# 10_FPGA_power.net
KiCad netlist of a schematic drawn in Altium Designer
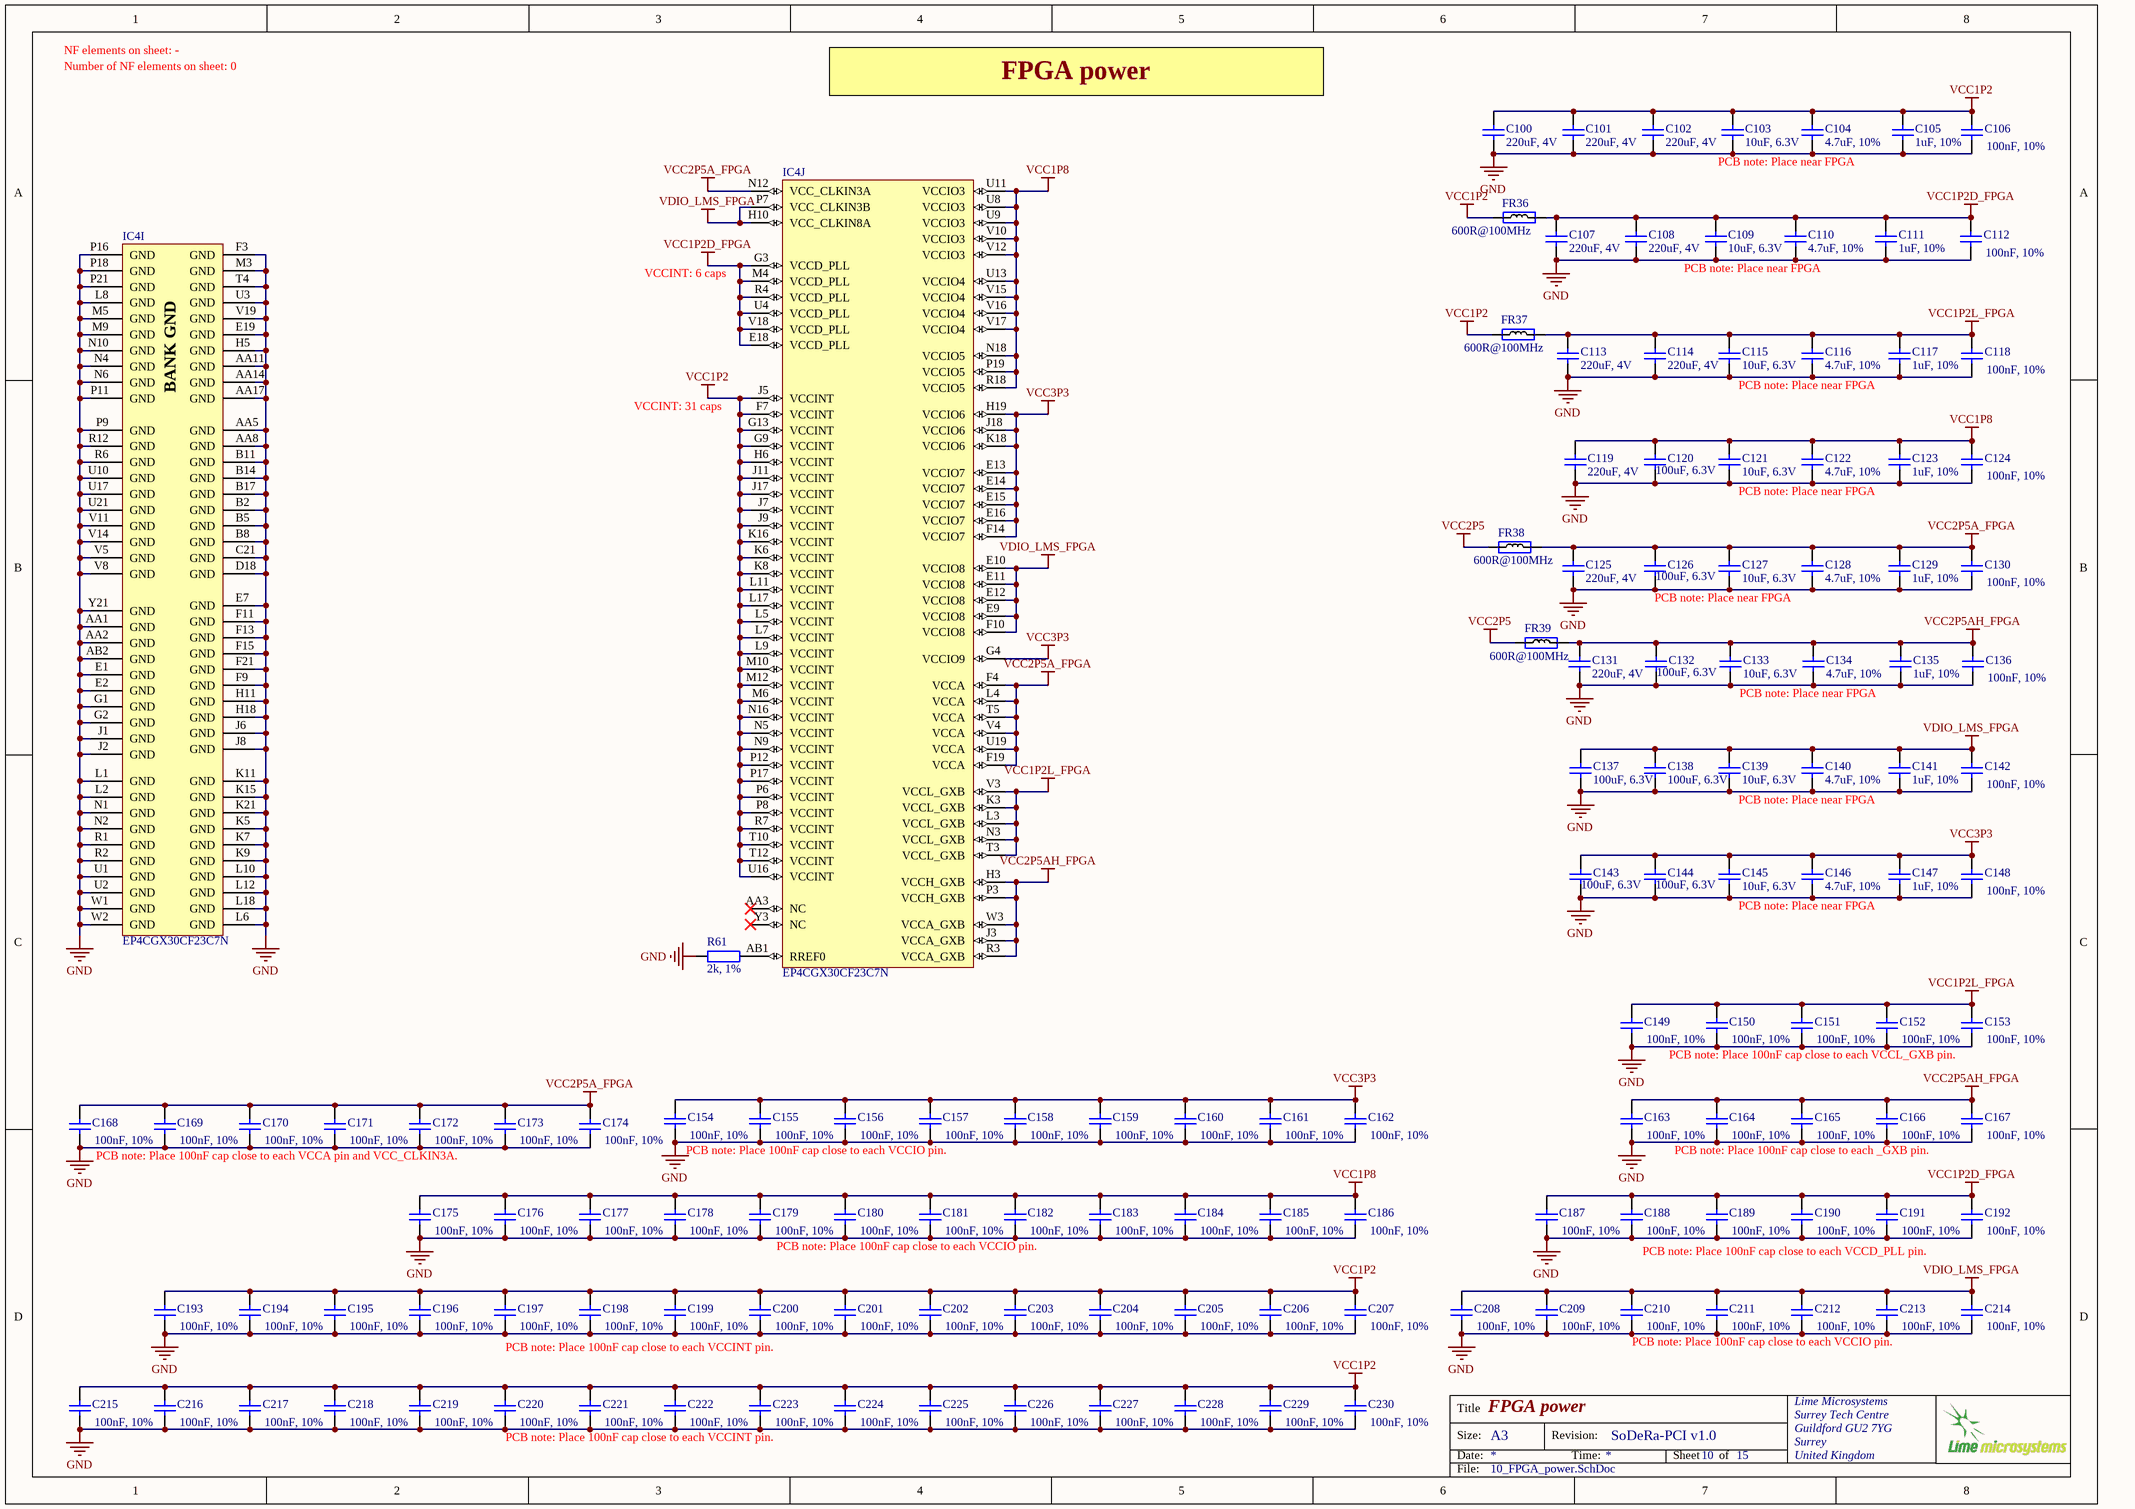
[diagram p0: 10_FPGA_power.SchDoc]

(export (version "E")
  (design (tool "Eeschema 10.0.6"))
  (components
    (comp (ref "C100")
      (value "220uF, 4V")
      (footprint "LimeMicroAltiumLib_pcbLib:CAP1206")
      (fields
        (field (name "MANUFACTURER PART NUMBER") "GRM31CR60G227ME11L")
        (field (name "MANUFACTURER") "Murata Electronics North America")
        (field (name "TOLERANCE") "±20%")
      )
      (libsource (lib "LimeFPGAboard_schLib") (part "Cap_1206"))
    )
    (comp (ref "C101")
      (value "220uF, 4V")
      (footprint "LimeMicroAltiumLib_pcbLib:CAP1206")
      (fields
        (field (name "MANUFACTURER PART NUMBER") "GRM31CR60G227ME11L")
        (field (name "MANUFACTURER") "Murata Electronics North America")
        (field (name "TOLERANCE") "±20%")
      )
      (libsource (lib "LimeFPGAboard_schLib") (part "Cap_1206"))
    )
    (comp (ref "C102")
      (value "220uF, 4V")
      (footprint "LimeMicroAltiumLib_pcbLib:CAP1206")
      (fields
        (field (name "MANUFACTURER PART NUMBER") "GRM31CR60G227ME11L")
        (field (name "MANUFACTURER") "Murata Electronics North America")
        (field (name "TOLERANCE") "±20%")
      )
      (libsource (lib "LimeFPGAboard_schLib") (part "Cap_1206"))
    )
    (comp (ref "C103")
      (value "10uF, 6.3V")
      (footprint "LimeMicroAltiumLib_pcbLib:CAP0603")
      (fields (field (name "TOLERANCE") "±20%"))
      (libsource (lib "LimeFPGAboard_schLib") (part "Cap_0603"))
    )
    (comp (ref "C104")
      (value "4.7uF, 10%")
      (footprint "LimeMicroAltiumLib_pcbLib:CAP0603")
      (fields (field (name "TOLERANCE") "10 %"))
      (libsource (lib "LimeFPGAboard_schLib") (part "Cap_0603"))
    )
    (comp (ref "C105")
      (value "1uF, 10%")
      (footprint "LimeMicroAltiumLib_pcbLib:CAP0402")
      (fields (field (name "MANUFACTURER") "TDK"))
      (libsource (lib "LimeMicroAltiumLib_schLib") (part "Cap_0402"))
    )
    (comp (ref "C106")
      (value "100nF, 10%")
      (footprint "LimeMicroAltiumLib_pcbLib:CAP0402")
      (fields
        (field (name "TOLERANCE") "10 %")
        (field (name "MANUFACTURER") "Murata")
        (field (name "MANUFACTURER PART NUMBER") "GRM155R71C104KA88D")
      )
      (libsource (lib "LimeFPGAboard_schLib") (part "Cap_0603"))
    )
    (comp (ref "C107")
      (value "220uF, 4V")
      (footprint "LimeMicroAltiumLib_pcbLib:CAP1206")
      (fields
        (field (name "MANUFACTURER PART NUMBER") "GRM31CR60G227ME11L")
        (field (name "MANUFACTURER") "Murata Electronics North America")
        (field (name "TOLERANCE") "±20%")
      )
      (libsource (lib "LimeFPGAboard_schLib") (part "Cap_1206"))
    )
    (comp (ref "C108")
      (value "220uF, 4V")
      (footprint "LimeMicroAltiumLib_pcbLib:CAP1206")
      (fields
        (field (name "MANUFACTURER PART NUMBER") "GRM31CR60G227ME11L")
        (field (name "MANUFACTURER") "Murata Electronics North America")
        (field (name "TOLERANCE") "±20%")
      )
      (libsource (lib "LimeFPGAboard_schLib") (part "Cap_1206"))
    )
    (comp (ref "C109")
      (value "10uF, 6.3V")
      (footprint "LimeMicroAltiumLib_pcbLib:CAP0603")
      (fields (field (name "TOLERANCE") "±20%"))
      (libsource (lib "LimeFPGAboard_schLib") (part "Cap_0603"))
    )
    (comp (ref "C110")
      (value "4.7uF, 10%")
      (footprint "LimeMicroAltiumLib_pcbLib:CAP0603")
      (fields (field (name "TOLERANCE") "10 %"))
      (libsource (lib "LimeFPGAboard_schLib") (part "Cap_0603"))
    )
    (comp (ref "C111")
      (value "1uF, 10%")
      (footprint "LimeMicroAltiumLib_pcbLib:CAP0402")
      (fields (field (name "MANUFACTURER") "TDK"))
      (libsource (lib "LimeMicroAltiumLib_schLib") (part "Cap_0402"))
    )
    (comp (ref "C112")
      (value "100nF, 10%")
      (footprint "LimeMicroAltiumLib_pcbLib:CAP0402")
      (fields
        (field (name "TOLERANCE") "10 %")
        (field (name "MANUFACTURER") "Murata")
        (field (name "MANUFACTURER PART NUMBER") "GRM155R71C104KA88D")
      )
      (libsource (lib "LimeFPGAboard_schLib") (part "Cap_0603"))
    )
    (comp (ref "C113")
      (value "220uF, 4V")
      (footprint "LimeMicroAltiumLib_pcbLib:CAP1206")
      (fields
        (field (name "MANUFACTURER PART NUMBER") "GRM31CR60G227ME11L")
        (field (name "MANUFACTURER") "Murata Electronics North America")
        (field (name "TOLERANCE") "±20%")
      )
      (libsource (lib "LimeFPGAboard_schLib") (part "Cap_1206"))
    )
    (comp (ref "C114")
      (value "220uF, 4V")
      (footprint "LimeMicroAltiumLib_pcbLib:CAP1206")
      (fields
        (field (name "MANUFACTURER PART NUMBER") "GRM31CR60G227ME11L")
        (field (name "MANUFACTURER") "Murata Electronics North America")
        (field (name "TOLERANCE") "±20%")
      )
      (libsource (lib "LimeFPGAboard_schLib") (part "Cap_1206"))
    )
    (comp (ref "C115")
      (value "10uF, 6.3V")
      (footprint "LimeMicroAltiumLib_pcbLib:CAP0603")
      (fields (field (name "TOLERANCE") "±20%"))
      (libsource (lib "LimeFPGAboard_schLib") (part "Cap_0603"))
    )
    (comp (ref "C116")
      (value "4.7uF, 10%")
      (footprint "LimeMicroAltiumLib_pcbLib:CAP0603")
      (fields (field (name "TOLERANCE") "10 %"))
      (libsource (lib "LimeFPGAboard_schLib") (part "Cap_0603"))
    )
    (comp (ref "C117")
      (value "1uF, 10%")
      (footprint "LimeMicroAltiumLib_pcbLib:CAP0402")
      (fields (field (name "MANUFACTURER") "TDK"))
      (libsource (lib "LimeMicroAltiumLib_schLib") (part "Cap_0402"))
    )
    (comp (ref "C118")
      (value "100nF, 10%")
      (footprint "LimeMicroAltiumLib_pcbLib:CAP0402")
      (fields
        (field (name "TOLERANCE") "10 %")
        (field (name "MANUFACTURER") "Murata")
        (field (name "MANUFACTURER PART NUMBER") "GRM155R71C104KA88D")
      )
      (libsource (lib "LimeFPGAboard_schLib") (part "Cap_0603"))
    )
    (comp (ref "C119")
      (value "220uF, 4V")
      (footprint "LimeMicroAltiumLib_pcbLib:CAP1206")
      (fields
        (field (name "MANUFACTURER PART NUMBER") "GRM31CR60G227ME11L")
        (field (name "MANUFACTURER") "Murata Electronics North America")
        (field (name "TOLERANCE") "±20%")
      )
      (libsource (lib "LimeFPGAboard_schLib") (part "Cap_1206"))
    )
    (comp (ref "C120")
      (value "100uF, 6.3V")
      (footprint "LimeMicroAltiumLib_pcbLib:CAP1206")
      (fields (field (name "MANUFACTURER") "MURATA"))
      (libsource (lib "LimeFPGAboard_schLib") (part "Cap_1206"))
    )
    (comp (ref "C121")
      (value "10uF, 6.3V")
      (footprint "LimeMicroAltiumLib_pcbLib:CAP0603")
      (fields (field (name "TOLERANCE") "±20%"))
      (libsource (lib "LimeFPGAboard_schLib") (part "Cap_0603"))
    )
    (comp (ref "C122")
      (value "4.7uF, 10%")
      (footprint "LimeMicroAltiumLib_pcbLib:CAP0603")
      (fields (field (name "TOLERANCE") "10 %"))
      (libsource (lib "LimeFPGAboard_schLib") (part "Cap_0603"))
    )
    (comp (ref "C123")
      (value "1uF, 10%")
      (footprint "LimeMicroAltiumLib_pcbLib:CAP0402")
      (fields (field (name "MANUFACTURER") "TDK"))
      (libsource (lib "LimeMicroAltiumLib_schLib") (part "Cap_0402"))
    )
    (comp (ref "C124")
      (value "100nF, 10%")
      (footprint "LimeMicroAltiumLib_pcbLib:CAP0402")
      (fields
        (field (name "TOLERANCE") "10 %")
        (field (name "MANUFACTURER") "Murata")
        (field (name "MANUFACTURER PART NUMBER") "GRM155R71C104KA88D")
      )
      (libsource (lib "LimeFPGAboard_schLib") (part "Cap_0603"))
    )
    (comp (ref "C125")
      (value "220uF, 4V")
      (footprint "LimeMicroAltiumLib_pcbLib:CAP1206")
      (fields
        (field (name "MANUFACTURER PART NUMBER") "GRM31CR60G227ME11L")
        (field (name "MANUFACTURER") "Murata Electronics North America")
        (field (name "TOLERANCE") "±20%")
      )
      (libsource (lib "LimeFPGAboard_schLib") (part "Cap_1206"))
    )
    (comp (ref "C126")
      (value "100uF, 6.3V")
      (footprint "LimeMicroAltiumLib_pcbLib:CAP1206")
      (fields (field (name "MANUFACTURER") "MURATA"))
      (libsource (lib "LimeFPGAboard_schLib") (part "Cap_1206"))
    )
    (comp (ref "C127")
      (value "10uF, 6.3V")
      (footprint "LimeMicroAltiumLib_pcbLib:CAP0603")
      (fields (field (name "TOLERANCE") "±20%"))
      (libsource (lib "LimeFPGAboard_schLib") (part "Cap_0603"))
    )
    (comp (ref "C128")
      (value "4.7uF, 10%")
      (footprint "LimeMicroAltiumLib_pcbLib:CAP0603")
      (fields (field (name "TOLERANCE") "10 %"))
      (libsource (lib "LimeFPGAboard_schLib") (part "Cap_0603"))
    )
    (comp (ref "C129")
      (value "1uF, 10%")
      (footprint "LimeMicroAltiumLib_pcbLib:CAP0402")
      (fields (field (name "MANUFACTURER") "TDK"))
      (libsource (lib "LimeMicroAltiumLib_schLib") (part "Cap_0402"))
    )
    (comp (ref "C130")
      (value "100nF, 10%")
      (footprint "LimeMicroAltiumLib_pcbLib:CAP0402")
      (fields
        (field (name "TOLERANCE") "10 %")
        (field (name "MANUFACTURER") "Murata")
        (field (name "MANUFACTURER PART NUMBER") "GRM155R71C104KA88D")
      )
      (libsource (lib "LimeFPGAboard_schLib") (part "Cap_0603"))
    )
    (comp (ref "C131")
      (value "220uF, 4V")
      (footprint "LimeMicroAltiumLib_pcbLib:CAP1206")
      (fields
        (field (name "MANUFACTURER PART NUMBER") "GRM31CR60G227ME11L")
        (field (name "MANUFACTURER") "Murata Electronics North America")
        (field (name "TOLERANCE") "±20%")
      )
      (libsource (lib "LimeFPGAboard_schLib") (part "Cap_1206"))
    )
    (comp (ref "C132")
      (value "100uF, 6.3V")
      (footprint "LimeMicroAltiumLib_pcbLib:CAP1206")
      (fields (field (name "MANUFACTURER") "MURATA"))
      (libsource (lib "LimeFPGAboard_schLib") (part "Cap_1206"))
    )
    (comp (ref "C133")
      (value "10uF, 6.3V")
      (footprint "LimeMicroAltiumLib_pcbLib:CAP0603")
      (fields (field (name "TOLERANCE") "±20%"))
      (libsource (lib "LimeFPGAboard_schLib") (part "Cap_0603"))
    )
    (comp (ref "C134")
      (value "4.7uF, 10%")
      (footprint "LimeMicroAltiumLib_pcbLib:CAP0603")
      (fields (field (name "TOLERANCE") "10 %"))
      (libsource (lib "LimeFPGAboard_schLib") (part "Cap_0603"))
    )
    (comp (ref "C135")
      (value "1uF, 10%")
      (footprint "LimeMicroAltiumLib_pcbLib:CAP0402")
      (fields (field (name "MANUFACTURER") "TDK"))
      (libsource (lib "LimeMicroAltiumLib_schLib") (part "Cap_0402"))
    )
    (comp (ref "C136")
      (value "100nF, 10%")
      (footprint "LimeMicroAltiumLib_pcbLib:CAP0402")
      (fields
        (field (name "TOLERANCE") "10 %")
        (field (name "MANUFACTURER") "Murata")
        (field (name "MANUFACTURER PART NUMBER") "GRM155R71C104KA88D")
      )
      (libsource (lib "LimeFPGAboard_schLib") (part "Cap_0603"))
    )
    (comp (ref "C137")
      (value "100uF, 6.3V")
      (footprint "LimeMicroAltiumLib_pcbLib:CAP1206")
      (fields (field (name "MANUFACTURER") "MURATA"))
      (libsource (lib "LimeFPGAboard_schLib") (part "Cap_1206"))
    )
    (comp (ref "C138")
      (value "100uF, 6.3V")
      (footprint "LimeMicroAltiumLib_pcbLib:CAP1206")
      (fields (field (name "MANUFACTURER") "MURATA"))
      (libsource (lib "LimeFPGAboard_schLib") (part "Cap_1206"))
    )
    (comp (ref "C139")
      (value "10uF, 6.3V")
      (footprint "LimeMicroAltiumLib_pcbLib:CAP0603")
      (fields (field (name "TOLERANCE") "±20%"))
      (libsource (lib "LimeFPGAboard_schLib") (part "Cap_0603"))
    )
    (comp (ref "C140")
      (value "4.7uF, 10%")
      (footprint "LimeMicroAltiumLib_pcbLib:CAP0603")
      (fields (field (name "TOLERANCE") "10 %"))
      (libsource (lib "LimeFPGAboard_schLib") (part "Cap_0603"))
    )
    (comp (ref "C141")
      (value "1uF, 10%")
      (footprint "LimeMicroAltiumLib_pcbLib:CAP0402")
      (fields (field (name "MANUFACTURER") "TDK"))
      (libsource (lib "LimeMicroAltiumLib_schLib") (part "Cap_0402"))
    )
    (comp (ref "C142")
      (value "100nF, 10%")
      (footprint "LimeMicroAltiumLib_pcbLib:CAP0402")
      (fields
        (field (name "TOLERANCE") "10 %")
        (field (name "MANUFACTURER") "Murata")
        (field (name "MANUFACTURER PART NUMBER") "GRM155R71C104KA88D")
      )
      (libsource (lib "LimeFPGAboard_schLib") (part "Cap_0603"))
    )
    (comp (ref "C143")
      (value "100uF, 6.3V")
      (footprint "LimeMicroAltiumLib_pcbLib:CAP1206")
      (fields (field (name "MANUFACTURER") "MURATA"))
      (libsource (lib "LimeFPGAboard_schLib") (part "Cap_1206"))
    )
    (comp (ref "C144")
      (value "100uF, 6.3V")
      (footprint "LimeMicroAltiumLib_pcbLib:CAP1206")
      (fields (field (name "MANUFACTURER") "MURATA"))
      (libsource (lib "LimeFPGAboard_schLib") (part "Cap_1206"))
    )
    (comp (ref "C145")
      (value "10uF, 6.3V")
      (footprint "LimeMicroAltiumLib_pcbLib:CAP0603")
      (fields (field (name "TOLERANCE") "±20%"))
      (libsource (lib "LimeFPGAboard_schLib") (part "Cap_0603"))
    )
    (comp (ref "C146")
      (value "4.7uF, 10%")
      (footprint "LimeMicroAltiumLib_pcbLib:CAP0603")
      (fields (field (name "TOLERANCE") "10 %"))
      (libsource (lib "LimeFPGAboard_schLib") (part "Cap_0603"))
    )
    (comp (ref "C147")
      (value "1uF, 10%")
      (footprint "LimeMicroAltiumLib_pcbLib:CAP0402")
      (fields (field (name "MANUFACTURER") "TDK"))
      (libsource (lib "LimeMicroAltiumLib_schLib") (part "Cap_0402"))
    )
    (comp (ref "C148")
      (value "100nF, 10%")
      (footprint "LimeMicroAltiumLib_pcbLib:CAP0402")
      (fields
        (field (name "TOLERANCE") "10 %")
        (field (name "MANUFACTURER") "Murata")
        (field (name "MANUFACTURER PART NUMBER") "GRM155R71C104KA88D")
      )
      (libsource (lib "LimeFPGAboard_schLib") (part "Cap_0603"))
    )
    (comp (ref "C149")
      (value "100nF, 10%")
      (footprint "LimeMicroAltiumLib_pcbLib:CAP0402")
      (fields
        (field (name "TOLERANCE") "10 %")
        (field (name "MANUFACTURER") "Murata")
        (field (name "MANUFACTURER PART NUMBER") "GRM155R71C104KA88D")
      )
      (libsource (lib "LimeFPGAboard_schLib") (part "Cap_0603"))
    )
    (comp (ref "C150")
      (value "100nF, 10%")
      (footprint "LimeMicroAltiumLib_pcbLib:CAP0402")
      (fields
        (field (name "TOLERANCE") "10 %")
        (field (name "MANUFACTURER") "Murata")
        (field (name "MANUFACTURER PART NUMBER") "GRM155R71C104KA88D")
      )
      (libsource (lib "LimeFPGAboard_schLib") (part "Cap_0603"))
    )
    (comp (ref "C151")
      (value "100nF, 10%")
      (footprint "LimeMicroAltiumLib_pcbLib:CAP0402")
      (fields
        (field (name "TOLERANCE") "10 %")
        (field (name "MANUFACTURER") "Murata")
        (field (name "MANUFACTURER PART NUMBER") "GRM155R71C104KA88D")
      )
      (libsource (lib "LimeFPGAboard_schLib") (part "Cap_0603"))
    )
    (comp (ref "C152")
      (value "100nF, 10%")
      (footprint "LimeMicroAltiumLib_pcbLib:CAP0402")
      (fields
        (field (name "TOLERANCE") "10 %")
        (field (name "MANUFACTURER") "Murata")
        (field (name "MANUFACTURER PART NUMBER") "GRM155R71C104KA88D")
      )
      (libsource (lib "LimeFPGAboard_schLib") (part "Cap_0603"))
    )
    (comp (ref "C153")
      (value "100nF, 10%")
      (footprint "LimeMicroAltiumLib_pcbLib:CAP0402")
      (fields
        (field (name "TOLERANCE") "10 %")
        (field (name "MANUFACTURER") "Murata")
        (field (name "MANUFACTURER PART NUMBER") "GRM155R71C104KA88D")
      )
      (libsource (lib "LimeFPGAboard_schLib") (part "Cap_0603"))
    )
    (comp (ref "C154")
      (value "100nF, 10%")
      (footprint "LimeMicroAltiumLib_pcbLib:CAP0402")
      (fields
        (field (name "TOLERANCE") "10 %")
        (field (name "MANUFACTURER") "Murata")
        (field (name "MANUFACTURER PART NUMBER") "GRM155R71C104KA88D")
      )
      (libsource (lib "LimeFPGAboard_schLib") (part "Cap_0603"))
    )
    (comp (ref "C155")
      (value "100nF, 10%")
      (footprint "LimeMicroAltiumLib_pcbLib:CAP0402")
      (fields
        (field (name "TOLERANCE") "10 %")
        (field (name "MANUFACTURER") "Murata")
        (field (name "MANUFACTURER PART NUMBER") "GRM155R71C104KA88D")
      )
      (libsource (lib "LimeFPGAboard_schLib") (part "Cap_0603"))
    )
    (comp (ref "C156")
      (value "100nF, 10%")
      (footprint "LimeMicroAltiumLib_pcbLib:CAP0402")
      (fields
        (field (name "TOLERANCE") "10 %")
        (field (name "MANUFACTURER") "Murata")
        (field (name "MANUFACTURER PART NUMBER") "GRM155R71C104KA88D")
      )
      (libsource (lib "LimeFPGAboard_schLib") (part "Cap_0603"))
    )
    (comp (ref "C157")
      (value "100nF, 10%")
      (footprint "LimeMicroAltiumLib_pcbLib:CAP0402")
      (fields
        (field (name "TOLERANCE") "10 %")
        (field (name "MANUFACTURER") "Murata")
        (field (name "MANUFACTURER PART NUMBER") "GRM155R71C104KA88D")
      )
      (libsource (lib "LimeFPGAboard_schLib") (part "Cap_0603"))
    )
    (comp (ref "C158")
      (value "100nF, 10%")
      (footprint "LimeMicroAltiumLib_pcbLib:CAP0402")
      (fields
        (field (name "TOLERANCE") "10 %")
        (field (name "MANUFACTURER") "Murata")
        (field (name "MANUFACTURER PART NUMBER") "GRM155R71C104KA88D")
      )
      (libsource (lib "LimeFPGAboard_schLib") (part "Cap_0603"))
    )
    (comp (ref "C159")
      (value "100nF, 10%")
      (footprint "LimeMicroAltiumLib_pcbLib:CAP0402")
      (fields
        (field (name "TOLERANCE") "10 %")
        (field (name "MANUFACTURER") "Murata")
        (field (name "MANUFACTURER PART NUMBER") "GRM155R71C104KA88D")
      )
      (libsource (lib "LimeFPGAboard_schLib") (part "Cap_0603"))
    )
    (comp (ref "C160")
      (value "100nF, 10%")
      (footprint "LimeMicroAltiumLib_pcbLib:CAP0402")
      (fields
        (field (name "TOLERANCE") "10 %")
        (field (name "MANUFACTURER") "Murata")
        (field (name "MANUFACTURER PART NUMBER") "GRM155R71C104KA88D")
      )
      (libsource (lib "LimeFPGAboard_schLib") (part "Cap_0603"))
    )
    (comp (ref "C161")
      (value "100nF, 10%")
      (footprint "LimeMicroAltiumLib_pcbLib:CAP0402")
      (fields
        (field (name "TOLERANCE") "10 %")
        (field (name "MANUFACTURER") "Murata")
        (field (name "MANUFACTURER PART NUMBER") "GRM155R71C104KA88D")
      )
      (libsource (lib "LimeFPGAboard_schLib") (part "Cap_0603"))
    )
    (comp (ref "C162")
      (value "100nF, 10%")
      (footprint "LimeMicroAltiumLib_pcbLib:CAP0402")
      (fields
        (field (name "TOLERANCE") "10 %")
        (field (name "MANUFACTURER") "Murata")
        (field (name "MANUFACTURER PART NUMBER") "GRM155R71C104KA88D")
      )
      (libsource (lib "LimeFPGAboard_schLib") (part "Cap_0603"))
    )
    (comp (ref "C163")
      (value "100nF, 10%")
      (footprint "LimeMicroAltiumLib_pcbLib:CAP0402")
      (fields
        (field (name "TOLERANCE") "10 %")
        (field (name "MANUFACTURER") "Murata")
        (field (name "MANUFACTURER PART NUMBER") "GRM155R71C104KA88D")
      )
      (libsource (lib "LimeFPGAboard_schLib") (part "Cap_0603"))
    )
    (comp (ref "C164")
      (value "100nF, 10%")
      (footprint "LimeMicroAltiumLib_pcbLib:CAP0402")
      (fields
        (field (name "TOLERANCE") "10 %")
        (field (name "MANUFACTURER") "Murata")
        (field (name "MANUFACTURER PART NUMBER") "GRM155R71C104KA88D")
      )
      (libsource (lib "LimeFPGAboard_schLib") (part "Cap_0603"))
    )
    (comp (ref "C165")
      (value "100nF, 10%")
      (footprint "LimeMicroAltiumLib_pcbLib:CAP0402")
      (fields
        (field (name "TOLERANCE") "10 %")
        (field (name "MANUFACTURER") "Murata")
        (field (name "MANUFACTURER PART NUMBER") "GRM155R71C104KA88D")
      )
      (libsource (lib "LimeFPGAboard_schLib") (part "Cap_0603"))
    )
    (comp (ref "C166")
      (value "100nF, 10%")
      (footprint "LimeMicroAltiumLib_pcbLib:CAP0402")
      (fields
        (field (name "TOLERANCE") "10 %")
        (field (name "MANUFACTURER") "Murata")
        (field (name "MANUFACTURER PART NUMBER") "GRM155R71C104KA88D")
      )
      (libsource (lib "LimeFPGAboard_schLib") (part "Cap_0603"))
    )
    (comp (ref "C167")
      (value "100nF, 10%")
      (footprint "LimeMicroAltiumLib_pcbLib:CAP0402")
      (fields
        (field (name "TOLERANCE") "10 %")
        (field (name "MANUFACTURER") "Murata")
        (field (name "MANUFACTURER PART NUMBER") "GRM155R71C104KA88D")
      )
      (libsource (lib "LimeFPGAboard_schLib") (part "Cap_0603"))
    )
    (comp (ref "C168")
      (value "100nF, 10%")
      (footprint "LimeMicroAltiumLib_pcbLib:CAP0402")
      (fields
        (field (name "TOLERANCE") "10 %")
        (field (name "MANUFACTURER") "Murata")
        (field (name "MANUFACTURER PART NUMBER") "GRM155R71C104KA88D")
      )
      (libsource (lib "LimeFPGAboard_schLib") (part "Cap_0603"))
    )
    (comp (ref "C169")
      (value "100nF, 10%")
      (footprint "LimeMicroAltiumLib_pcbLib:CAP0402")
      (fields
        (field (name "TOLERANCE") "10 %")
        (field (name "MANUFACTURER") "Murata")
        (field (name "MANUFACTURER PART NUMBER") "GRM155R71C104KA88D")
      )
      (libsource (lib "LimeFPGAboard_schLib") (part "Cap_0603"))
    )
    (comp (ref "C170")
      (value "100nF, 10%")
      (footprint "LimeMicroAltiumLib_pcbLib:CAP0402")
      (fields
        (field (name "TOLERANCE") "10 %")
        (field (name "MANUFACTURER") "Murata")
        (field (name "MANUFACTURER PART NUMBER") "GRM155R71C104KA88D")
      )
      (libsource (lib "LimeFPGAboard_schLib") (part "Cap_0603"))
    )
    (comp (ref "C171")
      (value "100nF, 10%")
      (footprint "LimeMicroAltiumLib_pcbLib:CAP0402")
      (fields
        (field (name "TOLERANCE") "10 %")
        (field (name "MANUFACTURER") "Murata")
        (field (name "MANUFACTURER PART NUMBER") "GRM155R71C104KA88D")
      )
      (libsource (lib "LimeFPGAboard_schLib") (part "Cap_0603"))
    )
    (comp (ref "C172")
      (value "100nF, 10%")
      (footprint "LimeMicroAltiumLib_pcbLib:CAP0402")
      (fields
        (field (name "TOLERANCE") "10 %")
        (field (name "MANUFACTURER") "Murata")
        (field (name "MANUFACTURER PART NUMBER") "GRM155R71C104KA88D")
      )
      (libsource (lib "LimeFPGAboard_schLib") (part "Cap_0603"))
    )
    (comp (ref "C173")
      (value "100nF, 10%")
      (footprint "LimeMicroAltiumLib_pcbLib:CAP0402")
      (fields
        (field (name "TOLERANCE") "10 %")
        (field (name "MANUFACTURER") "Murata")
        (field (name "MANUFACTURER PART NUMBER") "GRM155R71C104KA88D")
      )
      (libsource (lib "LimeFPGAboard_schLib") (part "Cap_0603"))
    )
    (comp (ref "C174")
      (value "100nF, 10%")
      (footprint "LimeMicroAltiumLib_pcbLib:CAP0402")
      (fields
        (field (name "TOLERANCE") "10 %")
        (field (name "MANUFACTURER") "Murata")
        (field (name "MANUFACTURER PART NUMBER") "GRM155R71C104KA88D")
      )
      (libsource (lib "LimeFPGAboard_schLib") (part "Cap_0603"))
    )
    (comp (ref "C175")
      (value "100nF, 10%")
      (footprint "LimeMicroAltiumLib_pcbLib:CAP0402")
      (fields
        (field (name "TOLERANCE") "10 %")
        (field (name "MANUFACTURER") "Murata")
        (field (name "MANUFACTURER PART NUMBER") "GRM155R71C104KA88D")
      )
      (libsource (lib "LimeFPGAboard_schLib") (part "Cap_0603"))
    )
    (comp (ref "C176")
      (value "100nF, 10%")
      (footprint "LimeMicroAltiumLib_pcbLib:CAP0402")
      (fields
        (field (name "TOLERANCE") "10 %")
        (field (name "MANUFACTURER") "Murata")
        (field (name "MANUFACTURER PART NUMBER") "GRM155R71C104KA88D")
      )
      (libsource (lib "LimeFPGAboard_schLib") (part "Cap_0603"))
    )
    (comp (ref "C177")
      (value "100nF, 10%")
      (footprint "LimeMicroAltiumLib_pcbLib:CAP0402")
      (fields
        (field (name "TOLERANCE") "10 %")
        (field (name "MANUFACTURER") "Murata")
        (field (name "MANUFACTURER PART NUMBER") "GRM155R71C104KA88D")
      )
      (libsource (lib "LimeFPGAboard_schLib") (part "Cap_0603"))
    )
    (comp (ref "C178")
      (value "100nF, 10%")
      (footprint "LimeMicroAltiumLib_pcbLib:CAP0402")
      (fields
        (field (name "TOLERANCE") "10 %")
        (field (name "MANUFACTURER") "Murata")
        (field (name "MANUFACTURER PART NUMBER") "GRM155R71C104KA88D")
      )
      (libsource (lib "LimeFPGAboard_schLib") (part "Cap_0603"))
    )
    (comp (ref "C179")
      (value "100nF, 10%")
      (footprint "LimeMicroAltiumLib_pcbLib:CAP0402")
      (fields
        (field (name "TOLERANCE") "10 %")
        (field (name "MANUFACTURER") "Murata")
        (field (name "MANUFACTURER PART NUMBER") "GRM155R71C104KA88D")
      )
      (libsource (lib "LimeFPGAboard_schLib") (part "Cap_0603"))
    )
    (comp (ref "C180")
      (value "100nF, 10%")
      (footprint "LimeMicroAltiumLib_pcbLib:CAP0402")
      (fields
        (field (name "TOLERANCE") "10 %")
        (field (name "MANUFACTURER") "Murata")
        (field (name "MANUFACTURER PART NUMBER") "GRM155R71C104KA88D")
      )
      (libsource (lib "LimeFPGAboard_schLib") (part "Cap_0603"))
    )
    (comp (ref "C181")
      (value "100nF, 10%")
      (footprint "LimeMicroAltiumLib_pcbLib:CAP0402")
      (fields
        (field (name "TOLERANCE") "10 %")
        (field (name "MANUFACTURER") "Murata")
        (field (name "MANUFACTURER PART NUMBER") "GRM155R71C104KA88D")
      )
      (libsource (lib "LimeFPGAboard_schLib") (part "Cap_0603"))
    )
    (comp (ref "C182")
      (value "100nF, 10%")
      (footprint "LimeMicroAltiumLib_pcbLib:CAP0402")
      (fields
        (field (name "TOLERANCE") "10 %")
        (field (name "MANUFACTURER") "Murata")
        (field (name "MANUFACTURER PART NUMBER") "GRM155R71C104KA88D")
      )
      (libsource (lib "LimeFPGAboard_schLib") (part "Cap_0603"))
    )
    (comp (ref "C183")
      (value "100nF, 10%")
      (footprint "LimeMicroAltiumLib_pcbLib:CAP0402")
      (fields
        (field (name "TOLERANCE") "10 %")
        (field (name "MANUFACTURER") "Murata")
        (field (name "MANUFACTURER PART NUMBER") "GRM155R71C104KA88D")
      )
      (libsource (lib "LimeFPGAboard_schLib") (part "Cap_0603"))
    )
    (comp (ref "C184")
      (value "100nF, 10%")
      (footprint "LimeMicroAltiumLib_pcbLib:CAP0402")
      (fields
        (field (name "TOLERANCE") "10 %")
        (field (name "MANUFACTURER") "Murata")
        (field (name "MANUFACTURER PART NUMBER") "GRM155R71C104KA88D")
      )
      (libsource (lib "LimeFPGAboard_schLib") (part "Cap_0603"))
    )
    (comp (ref "C185")
      (value "100nF, 10%")
      (footprint "LimeMicroAltiumLib_pcbLib:CAP0402")
      (fields
        (field (name "TOLERANCE") "10 %")
        (field (name "MANUFACTURER") "Murata")
        (field (name "MANUFACTURER PART NUMBER") "GRM155R71C104KA88D")
      )
      (libsource (lib "LimeFPGAboard_schLib") (part "Cap_0603"))
    )
    (comp (ref "C186")
      (value "100nF, 10%")
      (footprint "LimeMicroAltiumLib_pcbLib:CAP0402")
      (fields
        (field (name "TOLERANCE") "10 %")
        (field (name "MANUFACTURER") "Murata")
        (field (name "MANUFACTURER PART NUMBER") "GRM155R71C104KA88D")
      )
      (libsource (lib "LimeFPGAboard_schLib") (part "Cap_0603"))
    )
    (comp (ref "C187")
      (value "100nF, 10%")
      (footprint "LimeMicroAltiumLib_pcbLib:CAP0402")
      (fields
        (field (name "TOLERANCE") "10 %")
        (field (name "MANUFACTURER") "Murata")
        (field (name "MANUFACTURER PART NUMBER") "GRM155R71C104KA88D")
      )
      (libsource (lib "LimeFPGAboard_schLib") (part "Cap_0603"))
    )
    (comp (ref "C188")
      (value "100nF, 10%")
      (footprint "LimeMicroAltiumLib_pcbLib:CAP0402")
      (fields
        (field (name "TOLERANCE") "10 %")
        (field (name "MANUFACTURER") "Murata")
        (field (name "MANUFACTURER PART NUMBER") "GRM155R71C104KA88D")
      )
      (libsource (lib "LimeFPGAboard_schLib") (part "Cap_0603"))
    )
    (comp (ref "C189")
      (value "100nF, 10%")
      (footprint "LimeMicroAltiumLib_pcbLib:CAP0402")
      (fields
        (field (name "TOLERANCE") "10 %")
        (field (name "MANUFACTURER") "Murata")
        (field (name "MANUFACTURER PART NUMBER") "GRM155R71C104KA88D")
      )
      (libsource (lib "LimeFPGAboard_schLib") (part "Cap_0603"))
    )
    (comp (ref "C190")
      (value "100nF, 10%")
      (footprint "LimeMicroAltiumLib_pcbLib:CAP0402")
      (fields
        (field (name "TOLERANCE") "10 %")
        (field (name "MANUFACTURER") "Murata")
        (field (name "MANUFACTURER PART NUMBER") "GRM155R71C104KA88D")
      )
      (libsource (lib "LimeFPGAboard_schLib") (part "Cap_0603"))
    )
    (comp (ref "C191")
      (value "100nF, 10%")
      (footprint "LimeMicroAltiumLib_pcbLib:CAP0402")
      (fields
        (field (name "TOLERANCE") "10 %")
        (field (name "MANUFACTURER") "Murata")
        (field (name "MANUFACTURER PART NUMBER") "GRM155R71C104KA88D")
      )
      (libsource (lib "LimeFPGAboard_schLib") (part "Cap_0603"))
    )
    (comp (ref "C192")
      (value "100nF, 10%")
      (footprint "LimeMicroAltiumLib_pcbLib:CAP0402")
      (fields
        (field (name "TOLERANCE") "10 %")
        (field (name "MANUFACTURER") "Murata")
        (field (name "MANUFACTURER PART NUMBER") "GRM155R71C104KA88D")
      )
      (libsource (lib "LimeFPGAboard_schLib") (part "Cap_0603"))
    )
    (comp (ref "C193")
      (value "100nF, 10%")
      (footprint "LimeMicroAltiumLib_pcbLib:CAP0402")
      (fields
        (field (name "TOLERANCE") "10 %")
        (field (name "MANUFACTURER") "Murata")
        (field (name "MANUFACTURER PART NUMBER") "GRM155R71C104KA88D")
      )
      (libsource (lib "LimeFPGAboard_schLib") (part "Cap_0603"))
    )
    (comp (ref "C194")
      (value "100nF, 10%")
      (footprint "LimeMicroAltiumLib_pcbLib:CAP0402")
      (fields
        (field (name "TOLERANCE") "10 %")
        (field (name "MANUFACTURER") "Murata")
        (field (name "MANUFACTURER PART NUMBER") "GRM155R71C104KA88D")
      )
      (libsource (lib "LimeFPGAboard_schLib") (part "Cap_0603"))
    )
    (comp (ref "C195")
      (value "100nF, 10%")
      (footprint "LimeMicroAltiumLib_pcbLib:CAP0402")
      (fields
        (field (name "TOLERANCE") "10 %")
        (field (name "MANUFACTURER") "Murata")
        (field (name "MANUFACTURER PART NUMBER") "GRM155R71C104KA88D")
      )
      (libsource (lib "LimeFPGAboard_schLib") (part "Cap_0603"))
    )
    (comp (ref "C196")
      (value "100nF, 10%")
      (footprint "LimeMicroAltiumLib_pcbLib:CAP0402")
      (fields
        (field (name "TOLERANCE") "10 %")
        (field (name "MANUFACTURER") "Murata")
        (field (name "MANUFACTURER PART NUMBER") "GRM155R71C104KA88D")
      )
      (libsource (lib "LimeFPGAboard_schLib") (part "Cap_0603"))
    )
    (comp (ref "C197")
      (value "100nF, 10%")
      (footprint "LimeMicroAltiumLib_pcbLib:CAP0402")
      (fields
        (field (name "TOLERANCE") "10 %")
        (field (name "MANUFACTURER") "Murata")
        (field (name "MANUFACTURER PART NUMBER") "GRM155R71C104KA88D")
      )
      (libsource (lib "LimeFPGAboard_schLib") (part "Cap_0603"))
    )
    (comp (ref "C198")
      (value "100nF, 10%")
      (footprint "LimeMicroAltiumLib_pcbLib:CAP0402")
      (fields
        (field (name "TOLERANCE") "10 %")
        (field (name "MANUFACTURER") "Murata")
        (field (name "MANUFACTURER PART NUMBER") "GRM155R71C104KA88D")
      )
      (libsource (lib "LimeFPGAboard_schLib") (part "Cap_0603"))
    )
    (comp (ref "C199")
      (value "100nF, 10%")
      (footprint "LimeMicroAltiumLib_pcbLib:CAP0402")
      (fields
        (field (name "TOLERANCE") "10 %")
        (field (name "MANUFACTURER") "Murata")
        (field (name "MANUFACTURER PART NUMBER") "GRM155R71C104KA88D")
      )
      (libsource (lib "LimeFPGAboard_schLib") (part "Cap_0603"))
    )
    (comp (ref "C200")
      (value "100nF, 10%")
      (footprint "LimeMicroAltiumLib_pcbLib:CAP0402")
      (fields
        (field (name "TOLERANCE") "10 %")
        (field (name "MANUFACTURER") "Murata")
        (field (name "MANUFACTURER PART NUMBER") "GRM155R71C104KA88D")
      )
      (libsource (lib "LimeFPGAboard_schLib") (part "Cap_0603"))
    )
    (comp (ref "C201")
      (value "100nF, 10%")
      (footprint "LimeMicroAltiumLib_pcbLib:CAP0402")
      (fields
        (field (name "TOLERANCE") "10 %")
        (field (name "MANUFACTURER") "Murata")
        (field (name "MANUFACTURER PART NUMBER") "GRM155R71C104KA88D")
      )
      (libsource (lib "LimeFPGAboard_schLib") (part "Cap_0603"))
    )
    (comp (ref "C202")
      (value "100nF, 10%")
      (footprint "LimeMicroAltiumLib_pcbLib:CAP0402")
      (fields
        (field (name "TOLERANCE") "10 %")
        (field (name "MANUFACTURER") "Murata")
        (field (name "MANUFACTURER PART NUMBER") "GRM155R71C104KA88D")
      )
      (libsource (lib "LimeFPGAboard_schLib") (part "Cap_0603"))
    )
    (comp (ref "C203")
      (value "100nF, 10%")
      (footprint "LimeMicroAltiumLib_pcbLib:CAP0402")
      (fields
        (field (name "TOLERANCE") "10 %")
        (field (name "MANUFACTURER") "Murata")
        (field (name "MANUFACTURER PART NUMBER") "GRM155R71C104KA88D")
      )
      (libsource (lib "LimeFPGAboard_schLib") (part "Cap_0603"))
    )
    (comp (ref "C204")
      (value "100nF, 10%")
      (footprint "LimeMicroAltiumLib_pcbLib:CAP0402")
      (fields
        (field (name "TOLERANCE") "10 %")
        (field (name "MANUFACTURER") "Murata")
        (field (name "MANUFACTURER PART NUMBER") "GRM155R71C104KA88D")
      )
      (libsource (lib "LimeFPGAboard_schLib") (part "Cap_0603"))
    )
    (comp (ref "C205")
      (value "100nF, 10%")
      (footprint "LimeMicroAltiumLib_pcbLib:CAP0402")
      (fields
        (field (name "TOLERANCE") "10 %")
        (field (name "MANUFACTURER") "Murata")
        (field (name "MANUFACTURER PART NUMBER") "GRM155R71C104KA88D")
      )
      (libsource (lib "LimeFPGAboard_schLib") (part "Cap_0603"))
    )
    (comp (ref "C206")
      (value "100nF, 10%")
      (footprint "LimeMicroAltiumLib_pcbLib:CAP0402")
      (fields
        (field (name "TOLERANCE") "10 %")
        (field (name "MANUFACTURER") "Murata")
        (field (name "MANUFACTURER PART NUMBER") "GRM155R71C104KA88D")
      )
      (libsource (lib "LimeFPGAboard_schLib") (part "Cap_0603"))
    )
    (comp (ref "C207")
      (value "100nF, 10%")
      (footprint "LimeMicroAltiumLib_pcbLib:CAP0402")
      (fields
        (field (name "TOLERANCE") "10 %")
        (field (name "MANUFACTURER") "Murata")
        (field (name "MANUFACTURER PART NUMBER") "GRM155R71C104KA88D")
      )
      (libsource (lib "LimeFPGAboard_schLib") (part "Cap_0603"))
    )
    (comp (ref "C208")
      (value "100nF, 10%")
      (footprint "LimeMicroAltiumLib_pcbLib:CAP0402")
      (fields
        (field (name "TOLERANCE") "10 %")
        (field (name "MANUFACTURER") "Murata")
        (field (name "MANUFACTURER PART NUMBER") "GRM155R71C104KA88D")
      )
      (libsource (lib "LimeFPGAboard_schLib") (part "Cap_0603"))
    )
    (comp (ref "C209")
      (value "100nF, 10%")
      (footprint "LimeMicroAltiumLib_pcbLib:CAP0402")
      (fields
        (field (name "TOLERANCE") "10 %")
        (field (name "MANUFACTURER") "Murata")
        (field (name "MANUFACTURER PART NUMBER") "GRM155R71C104KA88D")
      )
      (libsource (lib "LimeFPGAboard_schLib") (part "Cap_0603"))
    )
    (comp (ref "C210")
      (value "100nF, 10%")
      (footprint "LimeMicroAltiumLib_pcbLib:CAP0402")
      (fields
        (field (name "TOLERANCE") "10 %")
        (field (name "MANUFACTURER") "Murata")
        (field (name "MANUFACTURER PART NUMBER") "GRM155R71C104KA88D")
      )
      (libsource (lib "LimeFPGAboard_schLib") (part "Cap_0603"))
    )
    (comp (ref "C211")
      (value "100nF, 10%")
      (footprint "LimeMicroAltiumLib_pcbLib:CAP0402")
      (fields
        (field (name "TOLERANCE") "10 %")
        (field (name "MANUFACTURER") "Murata")
        (field (name "MANUFACTURER PART NUMBER") "GRM155R71C104KA88D")
      )
      (libsource (lib "LimeFPGAboard_schLib") (part "Cap_0603"))
    )
    (comp (ref "C212")
      (value "100nF, 10%")
      (footprint "LimeMicroAltiumLib_pcbLib:CAP0402")
      (fields
        (field (name "TOLERANCE") "10 %")
        (field (name "MANUFACTURER") "Murata")
        (field (name "MANUFACTURER PART NUMBER") "GRM155R71C104KA88D")
      )
      (libsource (lib "LimeFPGAboard_schLib") (part "Cap_0603"))
    )
    (comp (ref "C213")
      (value "100nF, 10%")
      (footprint "LimeMicroAltiumLib_pcbLib:CAP0402")
      (fields
        (field (name "TOLERANCE") "10 %")
        (field (name "MANUFACTURER") "Murata")
        (field (name "MANUFACTURER PART NUMBER") "GRM155R71C104KA88D")
      )
      (libsource (lib "LimeFPGAboard_schLib") (part "Cap_0603"))
    )
    (comp (ref "C214")
      (value "100nF, 10%")
      (footprint "LimeMicroAltiumLib_pcbLib:CAP0402")
      (fields
        (field (name "TOLERANCE") "10 %")
        (field (name "MANUFACTURER") "Murata")
        (field (name "MANUFACTURER PART NUMBER") "GRM155R71C104KA88D")
      )
      (libsource (lib "LimeFPGAboard_schLib") (part "Cap_0603"))
    )
    (comp (ref "C215")
      (value "100nF, 10%")
      (footprint "LimeMicroAltiumLib_pcbLib:CAP0402")
      (fields
        (field (name "TOLERANCE") "10 %")
        (field (name "MANUFACTURER") "Murata")
        (field (name "MANUFACTURER PART NUMBER") "GRM155R71C104KA88D")
      )
      (libsource (lib "LimeFPGAboard_schLib") (part "Cap_0603"))
    )
    (comp (ref "C216")
      (value "100nF, 10%")
      (footprint "LimeMicroAltiumLib_pcbLib:CAP0402")
      (fields
        (field (name "TOLERANCE") "10 %")
        (field (name "MANUFACTURER") "Murata")
        (field (name "MANUFACTURER PART NUMBER") "GRM155R71C104KA88D")
      )
      (libsource (lib "LimeFPGAboard_schLib") (part "Cap_0603"))
    )
    (comp (ref "C217")
      (value "100nF, 10%")
      (footprint "LimeMicroAltiumLib_pcbLib:CAP0402")
      (fields
        (field (name "TOLERANCE") "10 %")
        (field (name "MANUFACTURER") "Murata")
        (field (name "MANUFACTURER PART NUMBER") "GRM155R71C104KA88D")
      )
      (libsource (lib "LimeFPGAboard_schLib") (part "Cap_0603"))
    )
    (comp (ref "C218")
      (value "100nF, 10%")
      (footprint "LimeMicroAltiumLib_pcbLib:CAP0402")
      (fields
        (field (name "TOLERANCE") "10 %")
        (field (name "MANUFACTURER") "Murata")
        (field (name "MANUFACTURER PART NUMBER") "GRM155R71C104KA88D")
      )
      (libsource (lib "LimeFPGAboard_schLib") (part "Cap_0603"))
    )
    (comp (ref "C219")
      (value "100nF, 10%")
      (footprint "LimeMicroAltiumLib_pcbLib:CAP0402")
      (fields
        (field (name "TOLERANCE") "10 %")
        (field (name "MANUFACTURER") "Murata")
        (field (name "MANUFACTURER PART NUMBER") "GRM155R71C104KA88D")
      )
      (libsource (lib "LimeFPGAboard_schLib") (part "Cap_0603"))
    )
    (comp (ref "C220")
      (value "100nF, 10%")
      (footprint "LimeMicroAltiumLib_pcbLib:CAP0402")
      (fields
        (field (name "TOLERANCE") "10 %")
        (field (name "MANUFACTURER") "Murata")
        (field (name "MANUFACTURER PART NUMBER") "GRM155R71C104KA88D")
      )
      (libsource (lib "LimeFPGAboard_schLib") (part "Cap_0603"))
    )
    (comp (ref "C221")
      (value "100nF, 10%")
      (footprint "LimeMicroAltiumLib_pcbLib:CAP0402")
      (fields
        (field (name "TOLERANCE") "10 %")
        (field (name "MANUFACTURER") "Murata")
        (field (name "MANUFACTURER PART NUMBER") "GRM155R71C104KA88D")
      )
      (libsource (lib "LimeFPGAboard_schLib") (part "Cap_0603"))
    )
    (comp (ref "C222")
      (value "100nF, 10%")
      (footprint "LimeMicroAltiumLib_pcbLib:CAP0402")
      (fields
        (field (name "TOLERANCE") "10 %")
        (field (name "MANUFACTURER") "Murata")
        (field (name "MANUFACTURER PART NUMBER") "GRM155R71C104KA88D")
      )
      (libsource (lib "LimeFPGAboard_schLib") (part "Cap_0603"))
    )
    (comp (ref "C223")
      (value "100nF, 10%")
      (footprint "LimeMicroAltiumLib_pcbLib:CAP0402")
      (fields
        (field (name "TOLERANCE") "10 %")
        (field (name "MANUFACTURER") "Murata")
        (field (name "MANUFACTURER PART NUMBER") "GRM155R71C104KA88D")
      )
      (libsource (lib "LimeFPGAboard_schLib") (part "Cap_0603"))
    )
    (comp (ref "C224")
      (value "100nF, 10%")
      (footprint "LimeMicroAltiumLib_pcbLib:CAP0402")
      (fields
        (field (name "TOLERANCE") "10 %")
        (field (name "MANUFACTURER") "Murata")
        (field (name "MANUFACTURER PART NUMBER") "GRM155R71C104KA88D")
      )
      (libsource (lib "LimeFPGAboard_schLib") (part "Cap_0603"))
    )
    (comp (ref "C225")
      (value "100nF, 10%")
      (footprint "LimeMicroAltiumLib_pcbLib:CAP0402")
      (fields
        (field (name "TOLERANCE") "10 %")
        (field (name "MANUFACTURER") "Murata")
        (field (name "MANUFACTURER PART NUMBER") "GRM155R71C104KA88D")
      )
      (libsource (lib "LimeFPGAboard_schLib") (part "Cap_0603"))
    )
    (comp (ref "C226")
      (value "100nF, 10%")
      (footprint "LimeMicroAltiumLib_pcbLib:CAP0402")
      (fields
        (field (name "TOLERANCE") "10 %")
        (field (name "MANUFACTURER") "Murata")
        (field (name "MANUFACTURER PART NUMBER") "GRM155R71C104KA88D")
      )
      (libsource (lib "LimeFPGAboard_schLib") (part "Cap_0603"))
    )
    (comp (ref "C227")
      (value "100nF, 10%")
      (footprint "LimeMicroAltiumLib_pcbLib:CAP0402")
      (fields
        (field (name "TOLERANCE") "10 %")
        (field (name "MANUFACTURER") "Murata")
        (field (name "MANUFACTURER PART NUMBER") "GRM155R71C104KA88D")
      )
      (libsource (lib "LimeFPGAboard_schLib") (part "Cap_0603"))
    )
    (comp (ref "C228")
      (value "100nF, 10%")
      (footprint "LimeMicroAltiumLib_pcbLib:CAP0402")
      (fields
        (field (name "TOLERANCE") "10 %")
        (field (name "MANUFACTURER") "Murata")
        (field (name "MANUFACTURER PART NUMBER") "GRM155R71C104KA88D")
      )
      (libsource (lib "LimeFPGAboard_schLib") (part "Cap_0603"))
    )
    (comp (ref "C229")
      (value "100nF, 10%")
      (footprint "LimeMicroAltiumLib_pcbLib:CAP0402")
      (fields
        (field (name "TOLERANCE") "10 %")
        (field (name "MANUFACTURER") "Murata")
        (field (name "MANUFACTURER PART NUMBER") "GRM155R71C104KA88D")
      )
      (libsource (lib "LimeFPGAboard_schLib") (part "Cap_0603"))
    )
    (comp (ref "C230")
      (value "100nF, 10%")
      (footprint "LimeMicroAltiumLib_pcbLib:CAP0402")
      (fields
        (field (name "TOLERANCE") "10 %")
        (field (name "MANUFACTURER") "Murata")
        (field (name "MANUFACTURER PART NUMBER") "GRM155R71C104KA88D")
      )
      (libsource (lib "LimeFPGAboard_schLib") (part "Cap_0603"))
    )
    (comp (ref "FR36")
      (value "600R@100MHz")
      (footprint "LimeMicroAltiumLib_pcbLib:RES0805")
      (fields (field (name "MANUFACTURER") "TDK Corporation"))
      (libsource (lib "LimeMicroAltiumLib_schLib") (part "Ferrite"))
    )
    (comp (ref "FR37")
      (value "600R@100MHz")
      (footprint "LimeMicroAltiumLib_pcbLib:RES0805")
      (fields (field (name "MANUFACTURER") "TDK Corporation"))
      (libsource (lib "LimeMicroAltiumLib_schLib") (part "Ferrite"))
    )
    (comp (ref "FR38")
      (value "600R@100MHz")
      (footprint "LimeMicroAltiumLib_pcbLib:RES0805")
      (fields (field (name "MANUFACTURER") "TDK Corporation"))
      (libsource (lib "LimeMicroAltiumLib_schLib") (part "Ferrite"))
    )
    (comp (ref "FR39")
      (value "600R@100MHz")
      (footprint "LimeMicroAltiumLib_pcbLib:RES0805")
      (fields (field (name "MANUFACTURER") "TDK Corporation"))
      (libsource (lib "LimeMicroAltiumLib_schLib") (part "Ferrite"))
    )
    (comp (ref "IC4")
      (value "EP4CGX30CF23C7N")
      (footprint "LimeMicroAltiumLib_pcbLib:ALTR-FBGA484_A-200")
      (fields (field (name "MANUFACTURER") "Altera"))
      (libsource (lib "LimeMicroAltiumLib_schLib") (part "EP4CGX30CF23C7N"))
    )
    (comp (ref "R61")
      (value "2k, 1%")
      (footprint "LimeMicroAltiumLib_pcbLib:RES0402")
      (fields
        (field (name "MANUFACTURER") "Yageo")
        (field (name "TOLERANCE") "±1%")
        (field (name "MANUFACTURER PART NUMBER") "RC0402FR-072KL")
      )
      (libsource (lib "LimeMicroAltiumLib_schLib") (part "Res_0402"))
    )
  )
  (nets
    (net (code "1") (name "GND") (class "Default")
      (node (ref "C100") (pin "1") (pinfunction "1_1") (pintype "passive"))
      (node (ref "C101") (pin "1") (pinfunction "1_1") (pintype "passive"))
      (node (ref "C102") (pin "1") (pinfunction "1_1") (pintype "passive"))
      (node (ref "C103") (pin "1") (pinfunction "1_1") (pintype "passive"))
      (node (ref "C104") (pin "1") (pinfunction "1_1") (pintype "passive"))
      (node (ref "C105") (pin "2") (pinfunction "2_2") (pintype "passive"))
      (node (ref "C106") (pin "2") (pinfunction "2_2") (pintype "passive"))
      (node (ref "C107") (pin "1") (pinfunction "1_1") (pintype "passive"))
      (node (ref "C108") (pin "1") (pinfunction "1_1") (pintype "passive"))
      (node (ref "C109") (pin "1") (pinfunction "1_1") (pintype "passive"))
      (node (ref "C110") (pin "1") (pinfunction "1_1") (pintype "passive"))
      (node (ref "C111") (pin "2") (pinfunction "2_2") (pintype "passive"))
      (node (ref "C112") (pin "2") (pinfunction "2_2") (pintype "passive"))
      (node (ref "C113") (pin "1") (pinfunction "1_1") (pintype "passive"))
      (node (ref "C114") (pin "1") (pinfunction "1_1") (pintype "passive"))
      (node (ref "C115") (pin "1") (pinfunction "1_1") (pintype "passive"))
      (node (ref "C116") (pin "1") (pinfunction "1_1") (pintype "passive"))
      (node (ref "C117") (pin "1") (pinfunction "1_1") (pintype "passive"))
      (node (ref "C118") (pin "2") (pinfunction "2_2") (pintype "passive"))
      (node (ref "C119") (pin "1") (pinfunction "1_1") (pintype "passive"))
      (node (ref "C120") (pin "1") (pinfunction "1_1") (pintype "passive"))
      (node (ref "C121") (pin "1") (pinfunction "1_1") (pintype "passive"))
      (node (ref "C122") (pin "1") (pinfunction "1_1") (pintype "passive"))
      (node (ref "C123") (pin "1") (pinfunction "1_1") (pintype "passive"))
      (node (ref "C124") (pin "2") (pinfunction "2_2") (pintype "passive"))
      (node (ref "C125") (pin "1") (pinfunction "1_1") (pintype "passive"))
      (node (ref "C126") (pin "1") (pinfunction "1_1") (pintype "passive"))
      (node (ref "C127") (pin "1") (pinfunction "1_1") (pintype "passive"))
      (node (ref "C128") (pin "1") (pinfunction "1_1") (pintype "passive"))
      (node (ref "C129") (pin "1") (pinfunction "1_1") (pintype "passive"))
      (node (ref "C130") (pin "2") (pinfunction "2_2") (pintype "passive"))
      (node (ref "C131") (pin "1") (pinfunction "1_1") (pintype "passive"))
      (node (ref "C132") (pin "1") (pinfunction "1_1") (pintype "passive"))
      (node (ref "C133") (pin "1") (pinfunction "1_1") (pintype "passive"))
      (node (ref "C134") (pin "1") (pinfunction "1_1") (pintype "passive"))
      (node (ref "C135") (pin "1") (pinfunction "1_1") (pintype "passive"))
      (node (ref "C136") (pin "2") (pinfunction "2_2") (pintype "passive"))
      (node (ref "C137") (pin "1") (pinfunction "1_1") (pintype "passive"))
      (node (ref "C138") (pin "1") (pinfunction "1_1") (pintype "passive"))
      (node (ref "C139") (pin "1") (pinfunction "1_1") (pintype "passive"))
      (node (ref "C140") (pin "1") (pinfunction "1_1") (pintype "passive"))
      (node (ref "C141") (pin "1") (pinfunction "1_1") (pintype "passive"))
      (node (ref "C142") (pin "2") (pinfunction "2_2") (pintype "passive"))
      (node (ref "C143") (pin "1") (pinfunction "1_1") (pintype "passive"))
      (node (ref "C144") (pin "1") (pinfunction "1_1") (pintype "passive"))
      (node (ref "C145") (pin "1") (pinfunction "1_1") (pintype "passive"))
      (node (ref "C146") (pin "1") (pinfunction "1_1") (pintype "passive"))
      (node (ref "C147") (pin "1") (pinfunction "1_1") (pintype "passive"))
      (node (ref "C148") (pin "2") (pinfunction "2_2") (pintype "passive"))
      (node (ref "C149") (pin "2") (pinfunction "2_2") (pintype "passive"))
      (node (ref "C150") (pin "2") (pinfunction "2_2") (pintype "passive"))
      (node (ref "C151") (pin "2") (pinfunction "2_2") (pintype "passive"))
      (node (ref "C152") (pin "2") (pinfunction "2_2") (pintype "passive"))
      (node (ref "C153") (pin "2") (pinfunction "2_2") (pintype "passive"))
      (node (ref "C154") (pin "2") (pinfunction "2_2") (pintype "passive"))
      (node (ref "C155") (pin "2") (pinfunction "2_2") (pintype "passive"))
      (node (ref "C156") (pin "2") (pinfunction "2_2") (pintype "passive"))
      (node (ref "C157") (pin "2") (pinfunction "2_2") (pintype "passive"))
      (node (ref "C158") (pin "2") (pinfunction "2_2") (pintype "passive"))
      (node (ref "C159") (pin "2") (pinfunction "2_2") (pintype "passive"))
      (node (ref "C160") (pin "2") (pinfunction "2_2") (pintype "passive"))
      (node (ref "C161") (pin "2") (pinfunction "2_2") (pintype "passive"))
      (node (ref "C162") (pin "2") (pinfunction "2_2") (pintype "passive"))
      (node (ref "C163") (pin "2") (pinfunction "2_2") (pintype "passive"))
      (node (ref "C164") (pin "2") (pinfunction "2_2") (pintype "passive"))
      (node (ref "C165") (pin "2") (pinfunction "2_2") (pintype "passive"))
      (node (ref "C166") (pin "2") (pinfunction "2_2") (pintype "passive"))
      (node (ref "C167") (pin "2") (pinfunction "2_2") (pintype "passive"))
      (node (ref "C168") (pin "2") (pinfunction "2_2") (pintype "passive"))
      (node (ref "C169") (pin "2") (pinfunction "2_2") (pintype "passive"))
      (node (ref "C170") (pin "2") (pinfunction "2_2") (pintype "passive"))
      (node (ref "C171") (pin "2") (pinfunction "2_2") (pintype "passive"))
      (node (ref "C172") (pin "2") (pinfunction "2_2") (pintype "passive"))
      (node (ref "C173") (pin "2") (pinfunction "2_2") (pintype "passive"))
      (node (ref "C174") (pin "2") (pinfunction "2_2") (pintype "passive"))
      (node (ref "C175") (pin "2") (pinfunction "2_2") (pintype "passive"))
      (node (ref "C176") (pin "2") (pinfunction "2_2") (pintype "passive"))
      (node (ref "C177") (pin "2") (pinfunction "2_2") (pintype "passive"))
      (node (ref "C178") (pin "2") (pinfunction "2_2") (pintype "passive"))
      (node (ref "C179") (pin "2") (pinfunction "2_2") (pintype "passive"))
      (node (ref "C180") (pin "2") (pinfunction "2_2") (pintype "passive"))
      (node (ref "C181") (pin "2") (pinfunction "2_2") (pintype "passive"))
      (node (ref "C182") (pin "2") (pinfunction "2_2") (pintype "passive"))
      (node (ref "C183") (pin "2") (pinfunction "2_2") (pintype "passive"))
      (node (ref "C184") (pin "2") (pinfunction "2_2") (pintype "passive"))
      (node (ref "C185") (pin "2") (pinfunction "2_2") (pintype "passive"))
      (node (ref "C186") (pin "2") (pinfunction "2_2") (pintype "passive"))
      (node (ref "C187") (pin "2") (pinfunction "2_2") (pintype "passive"))
      (node (ref "C188") (pin "2") (pinfunction "2_2") (pintype "passive"))
      (node (ref "C189") (pin "2") (pinfunction "2_2") (pintype "passive"))
      (node (ref "C190") (pin "2") (pinfunction "2_2") (pintype "passive"))
      (node (ref "C191") (pin "2") (pinfunction "2_2") (pintype "passive"))
      (node (ref "C192") (pin "2") (pinfunction "2_2") (pintype "passive"))
      (node (ref "C193") (pin "2") (pinfunction "2_2") (pintype "passive"))
      (node (ref "C194") (pin "2") (pinfunction "2_2") (pintype "passive"))
      (node (ref "C195") (pin "2") (pinfunction "2_2") (pintype "passive"))
      (node (ref "C196") (pin "2") (pinfunction "2_2") (pintype "passive"))
      (node (ref "C197") (pin "2") (pinfunction "2_2") (pintype "passive"))
      (node (ref "C198") (pin "2") (pinfunction "2_2") (pintype "passive"))
      (node (ref "C199") (pin "2") (pinfunction "2_2") (pintype "passive"))
      (node (ref "C200") (pin "2") (pinfunction "2_2") (pintype "passive"))
      (node (ref "C201") (pin "2") (pinfunction "2_2") (pintype "passive"))
      (node (ref "C202") (pin "2") (pinfunction "2_2") (pintype "passive"))
      (node (ref "C203") (pin "2") (pinfunction "2_2") (pintype "passive"))
      (node (ref "C204") (pin "2") (pinfunction "2_2") (pintype "passive"))
      (node (ref "C205") (pin "2") (pinfunction "2_2") (pintype "passive"))
      (node (ref "C206") (pin "2") (pinfunction "2_2") (pintype "passive"))
      (node (ref "C207") (pin "2") (pinfunction "2_2") (pintype "passive"))
      (node (ref "C208") (pin "2") (pinfunction "2_2") (pintype "passive"))
      (node (ref "C209") (pin "2") (pinfunction "2_2") (pintype "passive"))
      (node (ref "C210") (pin "2") (pinfunction "2_2") (pintype "passive"))
      (node (ref "C211") (pin "2") (pinfunction "2_2") (pintype "passive"))
      (node (ref "C212") (pin "2") (pinfunction "2_2") (pintype "passive"))
      (node (ref "C213") (pin "2") (pinfunction "2_2") (pintype "passive"))
      (node (ref "C214") (pin "2") (pinfunction "2_2") (pintype "passive"))
      (node (ref "C215") (pin "2") (pinfunction "2_2") (pintype "passive"))
      (node (ref "C216") (pin "2") (pinfunction "2_2") (pintype "passive"))
      (node (ref "C217") (pin "2") (pinfunction "2_2") (pintype "passive"))
      (node (ref "C218") (pin "2") (pinfunction "2_2") (pintype "passive"))
      (node (ref "C219") (pin "2") (pinfunction "2_2") (pintype "passive"))
      (node (ref "C220") (pin "2") (pinfunction "2_2") (pintype "passive"))
      (node (ref "C221") (pin "2") (pinfunction "2_2") (pintype "passive"))
      (node (ref "C222") (pin "2") (pinfunction "2_2") (pintype "passive"))
      (node (ref "C223") (pin "2") (pinfunction "2_2") (pintype "passive"))
      (node (ref "C224") (pin "2") (pinfunction "2_2") (pintype "passive"))
      (node (ref "C225") (pin "2") (pinfunction "2_2") (pintype "passive"))
      (node (ref "C226") (pin "2") (pinfunction "2_2") (pintype "passive"))
      (node (ref "C227") (pin "2") (pinfunction "2_2") (pintype "passive"))
      (node (ref "C228") (pin "2") (pinfunction "2_2") (pintype "passive"))
      (node (ref "C229") (pin "2") (pinfunction "2_2") (pintype "passive"))
      (node (ref "C230") (pin "2") (pinfunction "2_2") (pintype "passive"))
      (node (ref "IC4") (pin "AA1") (pinfunction "GND_AA1") (pintype "passive"))
      (node (ref "IC4") (pin "AA11") (pinfunction "GND_AA11") (pintype "passive"))
      (node (ref "IC4") (pin "AA14") (pinfunction "GND_AA14") (pintype "passive"))
      (node (ref "IC4") (pin "AA17") (pinfunction "GND_AA17") (pintype "passive"))
      (node (ref "IC4") (pin "AA2") (pinfunction "GND_AA2") (pintype "passive"))
      (node (ref "IC4") (pin "AA5") (pinfunction "GND_AA5") (pintype "passive"))
      (node (ref "IC4") (pin "AA8") (pinfunction "GND_AA8") (pintype "passive"))
      (node (ref "IC4") (pin "AB2") (pinfunction "GND_AB2") (pintype "passive"))
      (node (ref "IC4") (pin "B11") (pinfunction "GND_B11") (pintype "passive"))
      (node (ref "IC4") (pin "B14") (pinfunction "GND_B14") (pintype "passive"))
      (node (ref "IC4") (pin "B17") (pinfunction "GND_B17") (pintype "passive"))
      (node (ref "IC4") (pin "B2") (pinfunction "GND_B2") (pintype "passive"))
      (node (ref "IC4") (pin "B5") (pinfunction "GND_B5") (pintype "passive"))
      (node (ref "IC4") (pin "B8") (pinfunction "GND_B8") (pintype "passive"))
      (node (ref "IC4") (pin "C21") (pinfunction "GND_C21") (pintype "passive"))
      (node (ref "IC4") (pin "D18") (pinfunction "GND_D18") (pintype "passive"))
      (node (ref "IC4") (pin "E1") (pinfunction "GND_E1") (pintype "passive"))
      (node (ref "IC4") (pin "E19") (pinfunction "GND_E19") (pintype "passive"))
      (node (ref "IC4") (pin "E2") (pinfunction "GND_E2") (pintype "passive"))
      (node (ref "IC4") (pin "E7") (pinfunction "GND_E7") (pintype "passive"))
      (node (ref "IC4") (pin "F11") (pinfunction "GND_F11") (pintype "passive"))
      (node (ref "IC4") (pin "F13") (pinfunction "GND_F13") (pintype "passive"))
      (node (ref "IC4") (pin "F15") (pinfunction "GND_F15") (pintype "passive"))
      (node (ref "IC4") (pin "F21") (pinfunction "GND_F21") (pintype "passive"))
      (node (ref "IC4") (pin "F3") (pinfunction "GND_F3") (pintype "passive"))
      (node (ref "IC4") (pin "F9") (pinfunction "GND_F9") (pintype "passive"))
      (node (ref "IC4") (pin "G1") (pinfunction "GND_G1") (pintype "passive"))
      (node (ref "IC4") (pin "G2") (pinfunction "GND_G2") (pintype "passive"))
      (node (ref "IC4") (pin "H11") (pinfunction "GND_H11") (pintype "passive"))
      (node (ref "IC4") (pin "H18") (pinfunction "GND_H18") (pintype "passive"))
      (node (ref "IC4") (pin "H5") (pinfunction "GND_H5") (pintype "passive"))
      (node (ref "IC4") (pin "J1") (pinfunction "GND_J1") (pintype "passive"))
      (node (ref "IC4") (pin "J2") (pinfunction "GND_J2") (pintype "passive"))
      (node (ref "IC4") (pin "J6") (pinfunction "GND_J6") (pintype "passive"))
      (node (ref "IC4") (pin "J8") (pinfunction "GND_J8") (pintype "passive"))
      (node (ref "IC4") (pin "K11") (pinfunction "GND_K11") (pintype "passive"))
      (node (ref "IC4") (pin "K15") (pinfunction "GND_K15") (pintype "passive"))
      (node (ref "IC4") (pin "K21") (pinfunction "GND_K21") (pintype "passive"))
      (node (ref "IC4") (pin "K5") (pinfunction "GND_K5") (pintype "passive"))
      (node (ref "IC4") (pin "K7") (pinfunction "GND_K7") (pintype "passive"))
      (node (ref "IC4") (pin "K9") (pinfunction "GND_K9") (pintype "passive"))
      (node (ref "IC4") (pin "L1") (pinfunction "GND_L1") (pintype "passive"))
      (node (ref "IC4") (pin "L10") (pinfunction "GND_L10") (pintype "passive"))
      (node (ref "IC4") (pin "L12") (pinfunction "GND_L12") (pintype "passive"))
      (node (ref "IC4") (pin "L18") (pinfunction "GND_L18") (pintype "passive"))
      (node (ref "IC4") (pin "L2") (pinfunction "GND_L2") (pintype "passive"))
      (node (ref "IC4") (pin "L6") (pinfunction "GND_L6") (pintype "passive"))
      (node (ref "IC4") (pin "L8") (pinfunction "GND_L8") (pintype "passive"))
      (node (ref "IC4") (pin "M3") (pinfunction "GND_M3") (pintype "passive"))
      (node (ref "IC4") (pin "M5") (pinfunction "GND_M5") (pintype "passive"))
      (node (ref "IC4") (pin "M9") (pinfunction "GND_M9") (pintype "passive"))
      (node (ref "IC4") (pin "N1") (pinfunction "GND_N1") (pintype "passive"))
      (node (ref "IC4") (pin "N10") (pinfunction "GND_N10") (pintype "passive"))
      (node (ref "IC4") (pin "N2") (pinfunction "GND_N2") (pintype "passive"))
      (node (ref "IC4") (pin "N4") (pinfunction "GND_N4") (pintype "passive"))
      (node (ref "IC4") (pin "N6") (pinfunction "GND_N6") (pintype "passive"))
      (node (ref "IC4") (pin "P11") (pinfunction "GND_P11") (pintype "passive"))
      (node (ref "IC4") (pin "P16") (pinfunction "GND_P16") (pintype "passive"))
      (node (ref "IC4") (pin "P18") (pinfunction "GND_P18") (pintype "passive"))
      (node (ref "IC4") (pin "P21") (pinfunction "GND_P21") (pintype "passive"))
      (node (ref "IC4") (pin "P9") (pinfunction "GND_P9") (pintype "passive"))
      (node (ref "IC4") (pin "R1") (pinfunction "GND_R1") (pintype "passive"))
      (node (ref "IC4") (pin "R12") (pinfunction "GND_R12") (pintype "passive"))
      (node (ref "IC4") (pin "R2") (pinfunction "GND_R2") (pintype "passive"))
      (node (ref "IC4") (pin "R6") (pinfunction "GND_R6") (pintype "passive"))
      (node (ref "IC4") (pin "T4") (pinfunction "GND_T4") (pintype "passive"))
      (node (ref "IC4") (pin "U1") (pinfunction "GND_U1") (pintype "passive"))
      (node (ref "IC4") (pin "U10") (pinfunction "GND_U10") (pintype "passive"))
      (node (ref "IC4") (pin "U17") (pinfunction "GND_U17") (pintype "passive"))
      (node (ref "IC4") (pin "U2") (pinfunction "GND_U2") (pintype "passive"))
      (node (ref "IC4") (pin "U21") (pinfunction "GND_U21") (pintype "passive"))
      (node (ref "IC4") (pin "U3") (pinfunction "GND_U3") (pintype "passive"))
      (node (ref "IC4") (pin "V11") (pinfunction "GND_V11") (pintype "passive"))
      (node (ref "IC4") (pin "V14") (pinfunction "GND_V14") (pintype "passive"))
      (node (ref "IC4") (pin "V19") (pinfunction "GND_V19") (pintype "passive"))
      (node (ref "IC4") (pin "V5") (pinfunction "GND_V5") (pintype "passive"))
      (node (ref "IC4") (pin "V8") (pinfunction "GND_V8") (pintype "passive"))
      (node (ref "IC4") (pin "W1") (pinfunction "GND_W1") (pintype "passive"))
      (node (ref "IC4") (pin "W2") (pinfunction "GND_W2") (pintype "passive"))
      (node (ref "IC4") (pin "Y21") (pinfunction "GND_Y21") (pintype "passive"))
      (node (ref "R61") (pin "2") (pinfunction "2_2") (pintype "passive"))
    )
    (net (code "2") (name "Net-(IC4J-RREF0)") (class "Default")
      (node (ref "IC4") (pin "AB1") (pinfunction "RREF0_AB1") (pintype "bidirectional"))
      (node (ref "R61") (pin "1") (pinfunction "1_1") (pintype "passive"))
    )
    (net (code "3") (name "VCC1P2") (class "Default")
      (node (ref "C100") (pin "2") (pinfunction "2_2") (pintype "passive"))
      (node (ref "C101") (pin "2") (pinfunction "2_2") (pintype "passive"))
      (node (ref "C102") (pin "2") (pinfunction "2_2") (pintype "passive"))
      (node (ref "C103") (pin "2") (pinfunction "2_2") (pintype "passive"))
      (node (ref "C104") (pin "2") (pinfunction "2_2") (pintype "passive"))
      (node (ref "C105") (pin "1") (pinfunction "1_1") (pintype "passive"))
      (node (ref "C106") (pin "1") (pinfunction "1_1") (pintype "passive"))
      (node (ref "C193") (pin "1") (pinfunction "1_1") (pintype "passive"))
      (node (ref "C194") (pin "1") (pinfunction "1_1") (pintype "passive"))
      (node (ref "C195") (pin "1") (pinfunction "1_1") (pintype "passive"))
      (node (ref "C196") (pin "1") (pinfunction "1_1") (pintype "passive"))
      (node (ref "C197") (pin "1") (pinfunction "1_1") (pintype "passive"))
      (node (ref "C198") (pin "1") (pinfunction "1_1") (pintype "passive"))
      (node (ref "C199") (pin "1") (pinfunction "1_1") (pintype "passive"))
      (node (ref "C200") (pin "1") (pinfunction "1_1") (pintype "passive"))
      (node (ref "C201") (pin "1") (pinfunction "1_1") (pintype "passive"))
      (node (ref "C202") (pin "1") (pinfunction "1_1") (pintype "passive"))
      (node (ref "C203") (pin "1") (pinfunction "1_1") (pintype "passive"))
      (node (ref "C204") (pin "1") (pinfunction "1_1") (pintype "passive"))
      (node (ref "C205") (pin "1") (pinfunction "1_1") (pintype "passive"))
      (node (ref "C206") (pin "1") (pinfunction "1_1") (pintype "passive"))
      (node (ref "C207") (pin "1") (pinfunction "1_1") (pintype "passive"))
      (node (ref "C215") (pin "1") (pinfunction "1_1") (pintype "passive"))
      (node (ref "C216") (pin "1") (pinfunction "1_1") (pintype "passive"))
      (node (ref "C217") (pin "1") (pinfunction "1_1") (pintype "passive"))
      (node (ref "C218") (pin "1") (pinfunction "1_1") (pintype "passive"))
      (node (ref "C219") (pin "1") (pinfunction "1_1") (pintype "passive"))
      (node (ref "C220") (pin "1") (pinfunction "1_1") (pintype "passive"))
      (node (ref "C221") (pin "1") (pinfunction "1_1") (pintype "passive"))
      (node (ref "C222") (pin "1") (pinfunction "1_1") (pintype "passive"))
      (node (ref "C223") (pin "1") (pinfunction "1_1") (pintype "passive"))
      (node (ref "C224") (pin "1") (pinfunction "1_1") (pintype "passive"))
      (node (ref "C225") (pin "1") (pinfunction "1_1") (pintype "passive"))
      (node (ref "C226") (pin "1") (pinfunction "1_1") (pintype "passive"))
      (node (ref "C227") (pin "1") (pinfunction "1_1") (pintype "passive"))
      (node (ref "C228") (pin "1") (pinfunction "1_1") (pintype "passive"))
      (node (ref "C229") (pin "1") (pinfunction "1_1") (pintype "passive"))
      (node (ref "C230") (pin "1") (pinfunction "1_1") (pintype "passive"))
      (node (ref "FR36") (pin "1") (pinfunction "1_1") (pintype "passive"))
      (node (ref "FR37") (pin "1") (pinfunction "1_1") (pintype "passive"))
      (node (ref "IC4") (pin "F7") (pinfunction "VCCINT_F7") (pintype "bidirectional"))
      (node (ref "IC4") (pin "G13") (pinfunction "VCCINT_G13") (pintype "bidirectional"))
      (node (ref "IC4") (pin "G9") (pinfunction "VCCINT_G9") (pintype "bidirectional"))
      (node (ref "IC4") (pin "H6") (pinfunction "VCCINT_H6") (pintype "bidirectional"))
      (node (ref "IC4") (pin "J11") (pinfunction "VCCINT_J11") (pintype "bidirectional"))
      (node (ref "IC4") (pin "J17") (pinfunction "VCCINT_J17") (pintype "bidirectional"))
      (node (ref "IC4") (pin "J5") (pinfunction "VCCINT_J5") (pintype "bidirectional"))
      (node (ref "IC4") (pin "J7") (pinfunction "VCCINT_J7") (pintype "bidirectional"))
      (node (ref "IC4") (pin "J9") (pinfunction "VCCINT_J9") (pintype "bidirectional"))
      (node (ref "IC4") (pin "K16") (pinfunction "VCCINT_K16") (pintype "bidirectional"))
      (node (ref "IC4") (pin "K6") (pinfunction "VCCINT_K6") (pintype "bidirectional"))
      (node (ref "IC4") (pin "K8") (pinfunction "VCCINT_K8") (pintype "bidirectional"))
      (node (ref "IC4") (pin "L11") (pinfunction "VCCINT_L11") (pintype "bidirectional"))
      (node (ref "IC4") (pin "L17") (pinfunction "VCCINT_L17") (pintype "bidirectional"))
      (node (ref "IC4") (pin "L5") (pinfunction "VCCINT_L5") (pintype "bidirectional"))
      (node (ref "IC4") (pin "L7") (pinfunction "VCCINT_L7") (pintype "bidirectional"))
      (node (ref "IC4") (pin "L9") (pinfunction "VCCINT_L9") (pintype "bidirectional"))
      (node (ref "IC4") (pin "M10") (pinfunction "VCCINT_M10") (pintype "bidirectional"))
      (node (ref "IC4") (pin "M12") (pinfunction "VCCINT_M12") (pintype "bidirectional"))
      (node (ref "IC4") (pin "M6") (pinfunction "VCCINT_M6") (pintype "bidirectional"))
      (node (ref "IC4") (pin "N16") (pinfunction "VCCINT_N16") (pintype "bidirectional"))
      (node (ref "IC4") (pin "N5") (pinfunction "VCCINT_N5") (pintype "bidirectional"))
      (node (ref "IC4") (pin "N9") (pinfunction "VCCINT_N9") (pintype "bidirectional"))
      (node (ref "IC4") (pin "P12") (pinfunction "VCCINT_P12") (pintype "bidirectional"))
      (node (ref "IC4") (pin "P17") (pinfunction "VCCINT_P17") (pintype "bidirectional"))
      (node (ref "IC4") (pin "P6") (pinfunction "VCCINT_P6") (pintype "bidirectional"))
      (node (ref "IC4") (pin "P8") (pinfunction "VCCINT_P8") (pintype "bidirectional"))
      (node (ref "IC4") (pin "R7") (pinfunction "VCCINT_R7") (pintype "bidirectional"))
      (node (ref "IC4") (pin "T10") (pinfunction "VCCINT_T10") (pintype "bidirectional"))
      (node (ref "IC4") (pin "T12") (pinfunction "VCCINT_T12") (pintype "bidirectional"))
      (node (ref "IC4") (pin "U16") (pinfunction "VCCINT_U16") (pintype "bidirectional"))
    )
    (net (code "4") (name "VCC1P2D_FPGA") (class "Default")
      (node (ref "C107") (pin "2") (pinfunction "2_2") (pintype "passive"))
      (node (ref "C108") (pin "2") (pinfunction "2_2") (pintype "passive"))
      (node (ref "C109") (pin "2") (pinfunction "2_2") (pintype "passive"))
      (node (ref "C110") (pin "2") (pinfunction "2_2") (pintype "passive"))
      (node (ref "C111") (pin "1") (pinfunction "1_1") (pintype "passive"))
      (node (ref "C112") (pin "1") (pinfunction "1_1") (pintype "passive"))
      (node (ref "C187") (pin "1") (pinfunction "1_1") (pintype "passive"))
      (node (ref "C188") (pin "1") (pinfunction "1_1") (pintype "passive"))
      (node (ref "C189") (pin "1") (pinfunction "1_1") (pintype "passive"))
      (node (ref "C190") (pin "1") (pinfunction "1_1") (pintype "passive"))
      (node (ref "C191") (pin "1") (pinfunction "1_1") (pintype "passive"))
      (node (ref "C192") (pin "1") (pinfunction "1_1") (pintype "passive"))
      (node (ref "FR36") (pin "2") (pinfunction "2_2") (pintype "passive"))
      (node (ref "IC4") (pin "E18") (pinfunction "VCCD_PLL_E18") (pintype "bidirectional"))
      (node (ref "IC4") (pin "G3") (pinfunction "VCCD_PLL_G3") (pintype "bidirectional"))
      (node (ref "IC4") (pin "M4") (pinfunction "VCCD_PLL_M4") (pintype "bidirectional"))
      (node (ref "IC4") (pin "R4") (pinfunction "VCCD_PLL_R4") (pintype "bidirectional"))
      (node (ref "IC4") (pin "U4") (pinfunction "VCCD_PLL_U4") (pintype "bidirectional"))
      (node (ref "IC4") (pin "V18") (pinfunction "VCCD_PLL_V18") (pintype "bidirectional"))
    )
    (net (code "5") (name "VCC1P2L_FPGA") (class "Default")
      (node (ref "C113") (pin "2") (pinfunction "2_2") (pintype "passive"))
      (node (ref "C114") (pin "2") (pinfunction "2_2") (pintype "passive"))
      (node (ref "C115") (pin "2") (pinfunction "2_2") (pintype "passive"))
      (node (ref "C116") (pin "2") (pinfunction "2_2") (pintype "passive"))
      (node (ref "C117") (pin "2") (pinfunction "2_2") (pintype "passive"))
      (node (ref "C118") (pin "1") (pinfunction "1_1") (pintype "passive"))
      (node (ref "C149") (pin "1") (pinfunction "1_1") (pintype "passive"))
      (node (ref "C150") (pin "1") (pinfunction "1_1") (pintype "passive"))
      (node (ref "C151") (pin "1") (pinfunction "1_1") (pintype "passive"))
      (node (ref "C152") (pin "1") (pinfunction "1_1") (pintype "passive"))
      (node (ref "C153") (pin "1") (pinfunction "1_1") (pintype "passive"))
      (node (ref "FR37") (pin "2") (pinfunction "2_2") (pintype "passive"))
      (node (ref "IC4") (pin "K3") (pinfunction "VCCL_GXB_K3") (pintype "bidirectional"))
      (node (ref "IC4") (pin "L3") (pinfunction "VCCL_GXB_L3") (pintype "bidirectional"))
      (node (ref "IC4") (pin "N3") (pinfunction "VCCL_GXB_N3") (pintype "bidirectional"))
      (node (ref "IC4") (pin "T3") (pinfunction "VCCL_GXB_T3") (pintype "bidirectional"))
      (node (ref "IC4") (pin "V3") (pinfunction "VCCL_GXB_V3") (pintype "bidirectional"))
    )
    (net (code "6") (name "VCC1P8") (class "Default")
      (node (ref "C119") (pin "2") (pinfunction "2_2") (pintype "passive"))
      (node (ref "C120") (pin "2") (pinfunction "2_2") (pintype "passive"))
      (node (ref "C121") (pin "2") (pinfunction "2_2") (pintype "passive"))
      (node (ref "C122") (pin "2") (pinfunction "2_2") (pintype "passive"))
      (node (ref "C123") (pin "2") (pinfunction "2_2") (pintype "passive"))
      (node (ref "C124") (pin "1") (pinfunction "1_1") (pintype "passive"))
      (node (ref "C175") (pin "1") (pinfunction "1_1") (pintype "passive"))
      (node (ref "C176") (pin "1") (pinfunction "1_1") (pintype "passive"))
      (node (ref "C177") (pin "1") (pinfunction "1_1") (pintype "passive"))
      (node (ref "C178") (pin "1") (pinfunction "1_1") (pintype "passive"))
      (node (ref "C179") (pin "1") (pinfunction "1_1") (pintype "passive"))
      (node (ref "C180") (pin "1") (pinfunction "1_1") (pintype "passive"))
      (node (ref "C181") (pin "1") (pinfunction "1_1") (pintype "passive"))
      (node (ref "C182") (pin "1") (pinfunction "1_1") (pintype "passive"))
      (node (ref "C183") (pin "1") (pinfunction "1_1") (pintype "passive"))
      (node (ref "C184") (pin "1") (pinfunction "1_1") (pintype "passive"))
      (node (ref "C185") (pin "1") (pinfunction "1_1") (pintype "passive"))
      (node (ref "C186") (pin "1") (pinfunction "1_1") (pintype "passive"))
      (node (ref "IC4") (pin "N18") (pinfunction "VCCIO5_N18") (pintype "bidirectional"))
      (node (ref "IC4") (pin "P19") (pinfunction "VCCIO5_P19") (pintype "bidirectional"))
      (node (ref "IC4") (pin "R18") (pinfunction "VCCIO5_R18") (pintype "bidirectional"))
      (node (ref "IC4") (pin "U11") (pinfunction "VCCIO3_U11") (pintype "bidirectional"))
      (node (ref "IC4") (pin "U13") (pinfunction "VCCIO4_U13") (pintype "bidirectional"))
      (node (ref "IC4") (pin "U8") (pinfunction "VCCIO3_U8") (pintype "bidirectional"))
      (node (ref "IC4") (pin "U9") (pinfunction "VCCIO3_U9") (pintype "bidirectional"))
      (node (ref "IC4") (pin "V10") (pinfunction "VCCIO3_V10") (pintype "bidirectional"))
      (node (ref "IC4") (pin "V12") (pinfunction "VCCIO3_V12") (pintype "bidirectional"))
      (node (ref "IC4") (pin "V15") (pinfunction "VCCIO4_V15") (pintype "bidirectional"))
      (node (ref "IC4") (pin "V16") (pinfunction "VCCIO4_V16") (pintype "bidirectional"))
      (node (ref "IC4") (pin "V17") (pinfunction "VCCIO4_V17") (pintype "bidirectional"))
    )
    (net (code "7") (name "VCC2P5") (class "Default")
      (node (ref "FR38") (pin "1") (pinfunction "1_1") (pintype "passive"))
      (node (ref "FR39") (pin "1") (pinfunction "1_1") (pintype "passive"))
    )
    (net (code "8") (name "VCC2P5AH_FPGA") (class "Default")
      (node (ref "C131") (pin "2") (pinfunction "2_2") (pintype "passive"))
      (node (ref "C132") (pin "2") (pinfunction "2_2") (pintype "passive"))
      (node (ref "C133") (pin "2") (pinfunction "2_2") (pintype "passive"))
      (node (ref "C134") (pin "2") (pinfunction "2_2") (pintype "passive"))
      (node (ref "C135") (pin "2") (pinfunction "2_2") (pintype "passive"))
      (node (ref "C136") (pin "1") (pinfunction "1_1") (pintype "passive"))
      (node (ref "C163") (pin "1") (pinfunction "1_1") (pintype "passive"))
      (node (ref "C164") (pin "1") (pinfunction "1_1") (pintype "passive"))
      (node (ref "C165") (pin "1") (pinfunction "1_1") (pintype "passive"))
      (node (ref "C166") (pin "1") (pinfunction "1_1") (pintype "passive"))
      (node (ref "C167") (pin "1") (pinfunction "1_1") (pintype "passive"))
      (node (ref "FR39") (pin "2") (pinfunction "2_2") (pintype "passive"))
      (node (ref "IC4") (pin "H3") (pinfunction "VCCH_GXB_H3") (pintype "bidirectional"))
      (node (ref "IC4") (pin "J3") (pinfunction "VCCA_GXB_J3") (pintype "bidirectional"))
      (node (ref "IC4") (pin "P3") (pinfunction "VCCH_GXB_P3") (pintype "bidirectional"))
      (node (ref "IC4") (pin "R3") (pinfunction "VCCA_GXB_R3") (pintype "bidirectional"))
      (node (ref "IC4") (pin "W3") (pinfunction "VCCA_GXB_W3") (pintype "bidirectional"))
    )
    (net (code "9") (name "VCC2P5A_FPGA") (class "Default")
      (node (ref "C125") (pin "2") (pinfunction "2_2") (pintype "passive"))
      (node (ref "C126") (pin "2") (pinfunction "2_2") (pintype "passive"))
      (node (ref "C127") (pin "2") (pinfunction "2_2") (pintype "passive"))
      (node (ref "C128") (pin "2") (pinfunction "2_2") (pintype "passive"))
      (node (ref "C129") (pin "2") (pinfunction "2_2") (pintype "passive"))
      (node (ref "C130") (pin "1") (pinfunction "1_1") (pintype "passive"))
      (node (ref "C168") (pin "1") (pinfunction "1_1") (pintype "passive"))
      (node (ref "C169") (pin "1") (pinfunction "1_1") (pintype "passive"))
      (node (ref "C170") (pin "1") (pinfunction "1_1") (pintype "passive"))
      (node (ref "C171") (pin "1") (pinfunction "1_1") (pintype "passive"))
      (node (ref "C172") (pin "1") (pinfunction "1_1") (pintype "passive"))
      (node (ref "C173") (pin "1") (pinfunction "1_1") (pintype "passive"))
      (node (ref "C174") (pin "1") (pinfunction "1_1") (pintype "passive"))
      (node (ref "FR38") (pin "2") (pinfunction "2_2") (pintype "passive"))
      (node (ref "IC4") (pin "F19") (pinfunction "VCCA_F19") (pintype "bidirectional"))
      (node (ref "IC4") (pin "F4") (pinfunction "VCCA_F4") (pintype "bidirectional"))
      (node (ref "IC4") (pin "L4") (pinfunction "VCCA_L4") (pintype "bidirectional"))
      (node (ref "IC4") (pin "N12") (pinfunction "VCC_CLKIN3A_N12") (pintype "bidirectional"))
      (node (ref "IC4") (pin "T5") (pinfunction "VCCA_T5") (pintype "bidirectional"))
      (node (ref "IC4") (pin "U19") (pinfunction "VCCA_U19") (pintype "bidirectional"))
      (node (ref "IC4") (pin "V4") (pinfunction "VCCA_V4") (pintype "bidirectional"))
    )
    (net (code "10") (name "VCC3P3") (class "Default")
      (node (ref "C143") (pin "2") (pinfunction "2_2") (pintype "passive"))
      (node (ref "C144") (pin "2") (pinfunction "2_2") (pintype "passive"))
      (node (ref "C145") (pin "2") (pinfunction "2_2") (pintype "passive"))
      (node (ref "C146") (pin "2") (pinfunction "2_2") (pintype "passive"))
      (node (ref "C147") (pin "2") (pinfunction "2_2") (pintype "passive"))
      (node (ref "C148") (pin "1") (pinfunction "1_1") (pintype "passive"))
      (node (ref "C154") (pin "1") (pinfunction "1_1") (pintype "passive"))
      (node (ref "C155") (pin "1") (pinfunction "1_1") (pintype "passive"))
      (node (ref "C156") (pin "1") (pinfunction "1_1") (pintype "passive"))
      (node (ref "C157") (pin "1") (pinfunction "1_1") (pintype "passive"))
      (node (ref "C158") (pin "1") (pinfunction "1_1") (pintype "passive"))
      (node (ref "C159") (pin "1") (pinfunction "1_1") (pintype "passive"))
      (node (ref "C160") (pin "1") (pinfunction "1_1") (pintype "passive"))
      (node (ref "C161") (pin "1") (pinfunction "1_1") (pintype "passive"))
      (node (ref "C162") (pin "1") (pinfunction "1_1") (pintype "passive"))
      (node (ref "IC4") (pin "E13") (pinfunction "VCCIO7_E13") (pintype "bidirectional"))
      (node (ref "IC4") (pin "E14") (pinfunction "VCCIO7_E14") (pintype "bidirectional"))
      (node (ref "IC4") (pin "E15") (pinfunction "VCCIO7_E15") (pintype "bidirectional"))
      (node (ref "IC4") (pin "E16") (pinfunction "VCCIO7_E16") (pintype "bidirectional"))
      (node (ref "IC4") (pin "F14") (pinfunction "VCCIO7_F14") (pintype "bidirectional"))
      (node (ref "IC4") (pin "G4") (pinfunction "VCCIO9_G4") (pintype "bidirectional"))
      (node (ref "IC4") (pin "H19") (pinfunction "VCCIO6_H19") (pintype "bidirectional"))
      (node (ref "IC4") (pin "J18") (pinfunction "VCCIO6_J18") (pintype "bidirectional"))
      (node (ref "IC4") (pin "K18") (pinfunction "VCCIO6_K18") (pintype "bidirectional"))
    )
    (net (code "11") (name "VDIO_LMS_FPGA") (class "Default")
      (node (ref "C137") (pin "2") (pinfunction "2_2") (pintype "passive"))
      (node (ref "C138") (pin "2") (pinfunction "2_2") (pintype "passive"))
      (node (ref "C139") (pin "2") (pinfunction "2_2") (pintype "passive"))
      (node (ref "C140") (pin "2") (pinfunction "2_2") (pintype "passive"))
      (node (ref "C141") (pin "2") (pinfunction "2_2") (pintype "passive"))
      (node (ref "C142") (pin "1") (pinfunction "1_1") (pintype "passive"))
      (node (ref "C208") (pin "1") (pinfunction "1_1") (pintype "passive"))
      (node (ref "C209") (pin "1") (pinfunction "1_1") (pintype "passive"))
      (node (ref "C210") (pin "1") (pinfunction "1_1") (pintype "passive"))
      (node (ref "C211") (pin "1") (pinfunction "1_1") (pintype "passive"))
      (node (ref "C212") (pin "1") (pinfunction "1_1") (pintype "passive"))
      (node (ref "C213") (pin "1") (pinfunction "1_1") (pintype "passive"))
      (node (ref "C214") (pin "1") (pinfunction "1_1") (pintype "passive"))
      (node (ref "IC4") (pin "E10") (pinfunction "VCCIO8_E10") (pintype "bidirectional"))
      (node (ref "IC4") (pin "E11") (pinfunction "VCCIO8_E11") (pintype "bidirectional"))
      (node (ref "IC4") (pin "E12") (pinfunction "VCCIO8_E12") (pintype "bidirectional"))
      (node (ref "IC4") (pin "E9") (pinfunction "VCCIO8_E9") (pintype "bidirectional"))
      (node (ref "IC4") (pin "F10") (pinfunction "VCCIO8_F10") (pintype "bidirectional"))
      (node (ref "IC4") (pin "H10") (pinfunction "VCC_CLKIN8A_H10") (pintype "bidirectional"))
      (node (ref "IC4") (pin "P7") (pinfunction "VCC_CLKIN3B_P7") (pintype "bidirectional"))
    )
    (net (code "12") (name "unconnected-(IC4J-NC-PadAA3)") (class "Default")
      (node (ref "IC4") (pin "AA3") (pinfunction "NC_AA3") (pintype "bidirectional+no_connect"))
    )
    (net (code "13") (name "unconnected-(IC4J-NC-PadY3)") (class "Default")
      (node (ref "IC4") (pin "Y3") (pinfunction "NC_Y3") (pintype "bidirectional+no_connect"))
    )
  )
)
